# obc.net
KiCad netlist of a schematic drawn in EAGLE
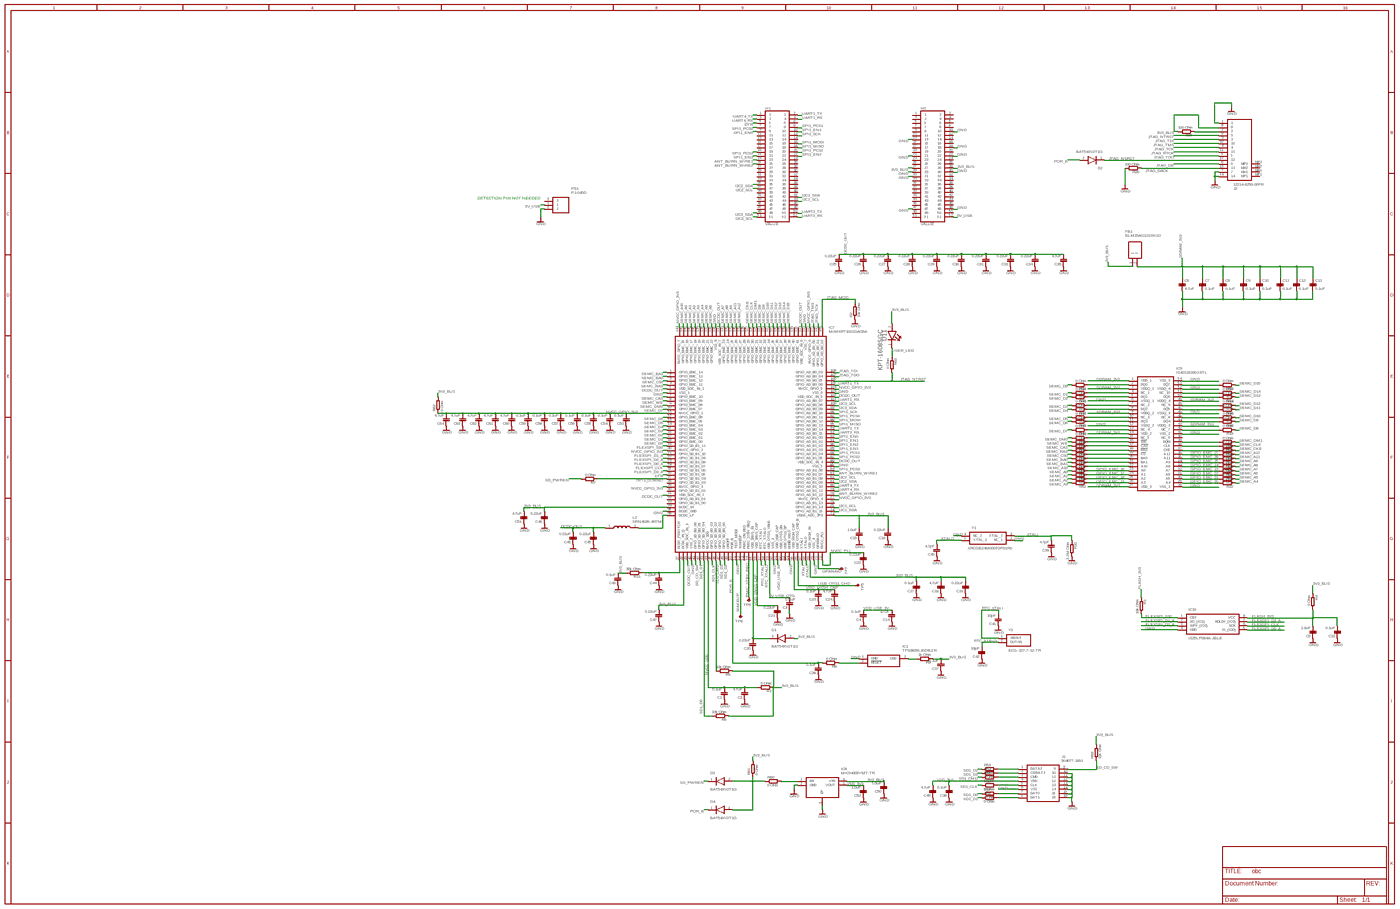
[diagram p0: schematic, sheet 1, overview]
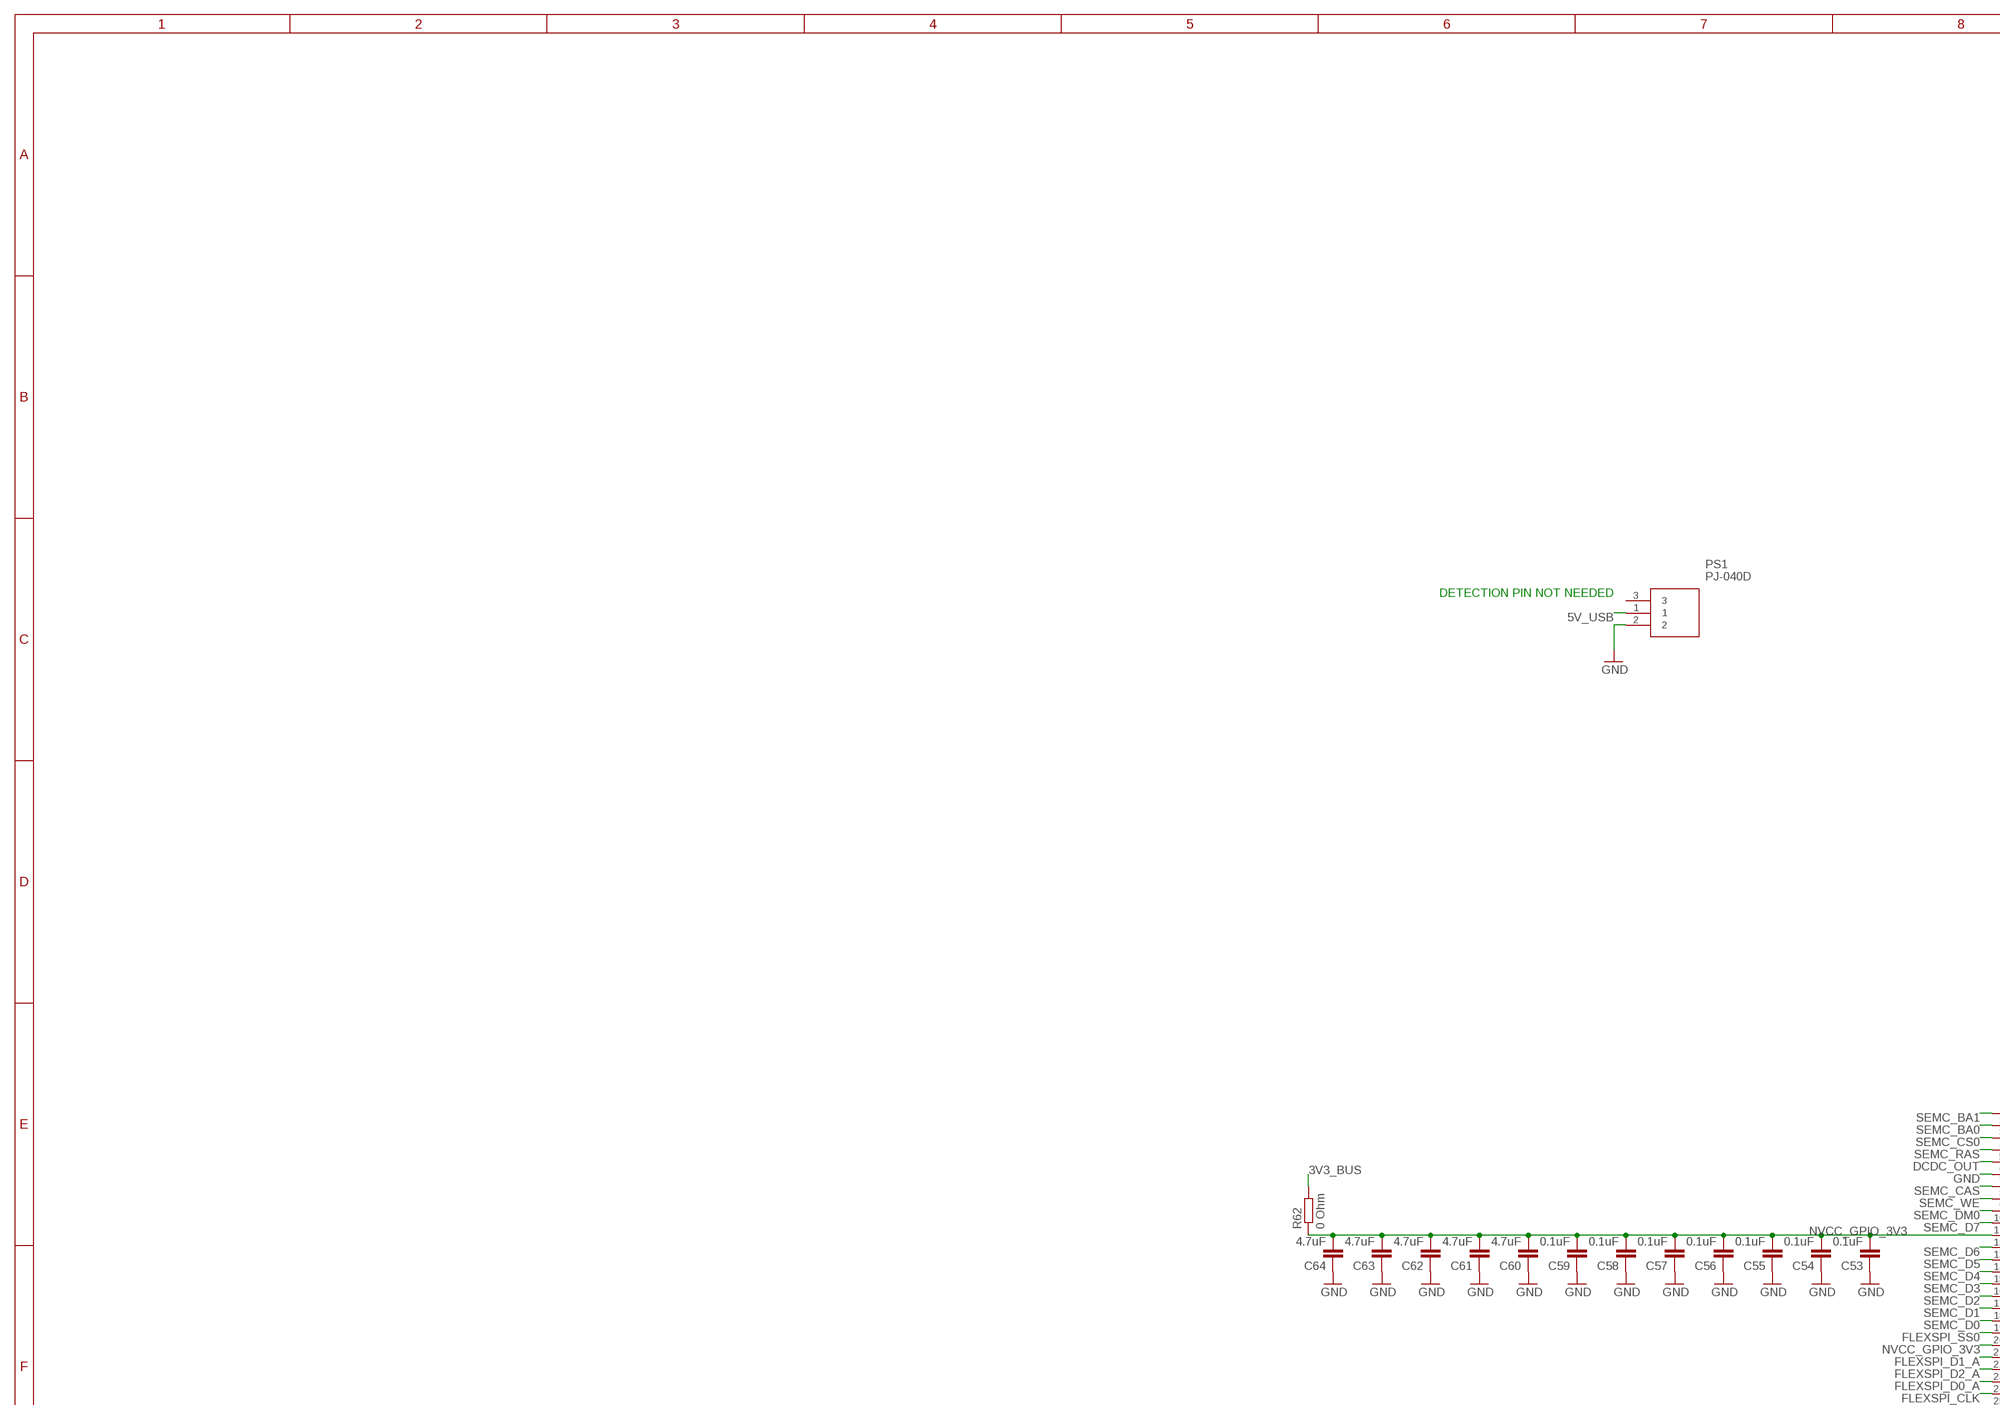
[diagram p1: schematic, sheet 1, part 1 of 4]
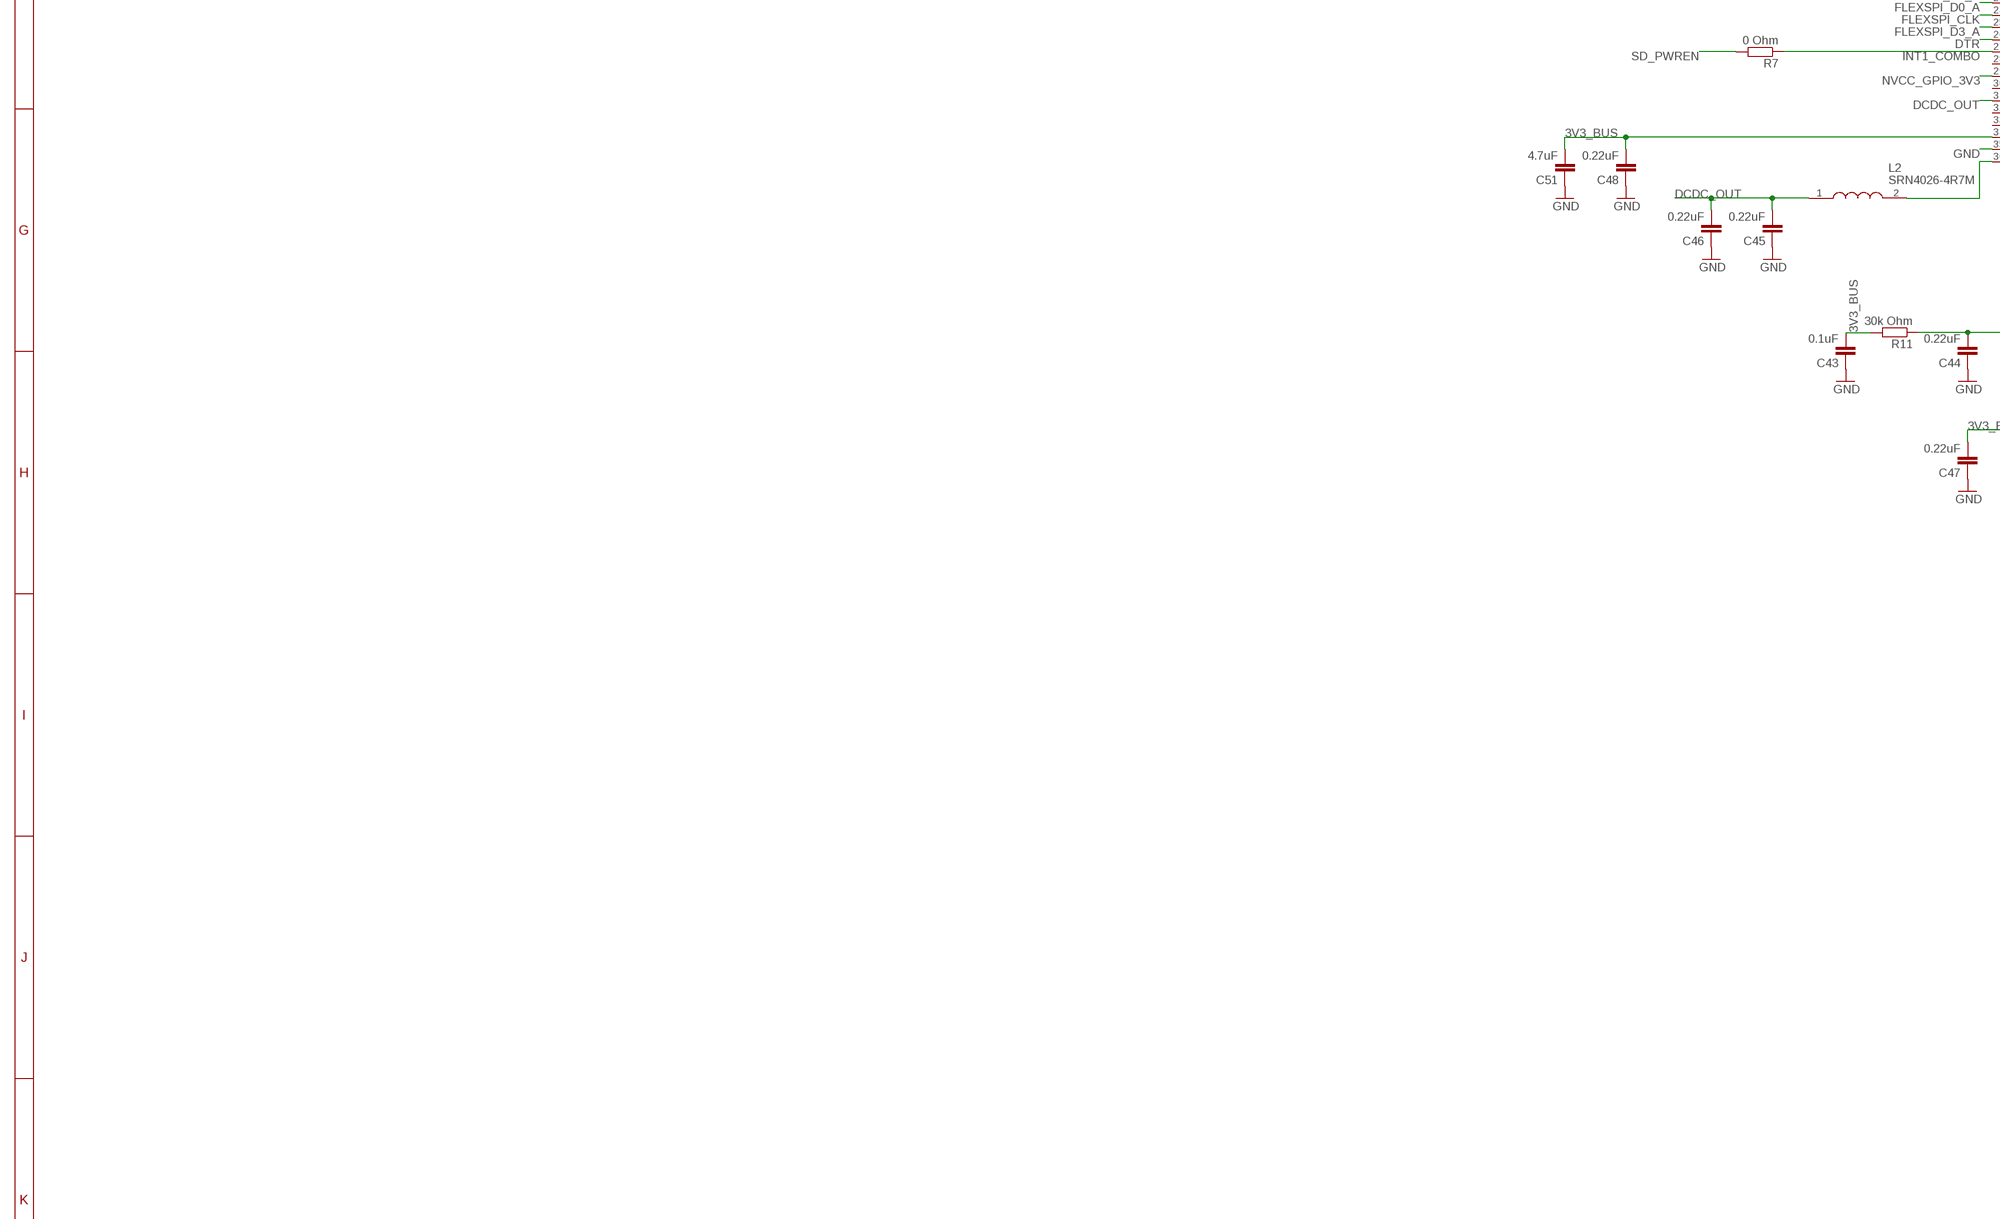
[diagram p2: schematic, sheet 1, part 2 of 4]
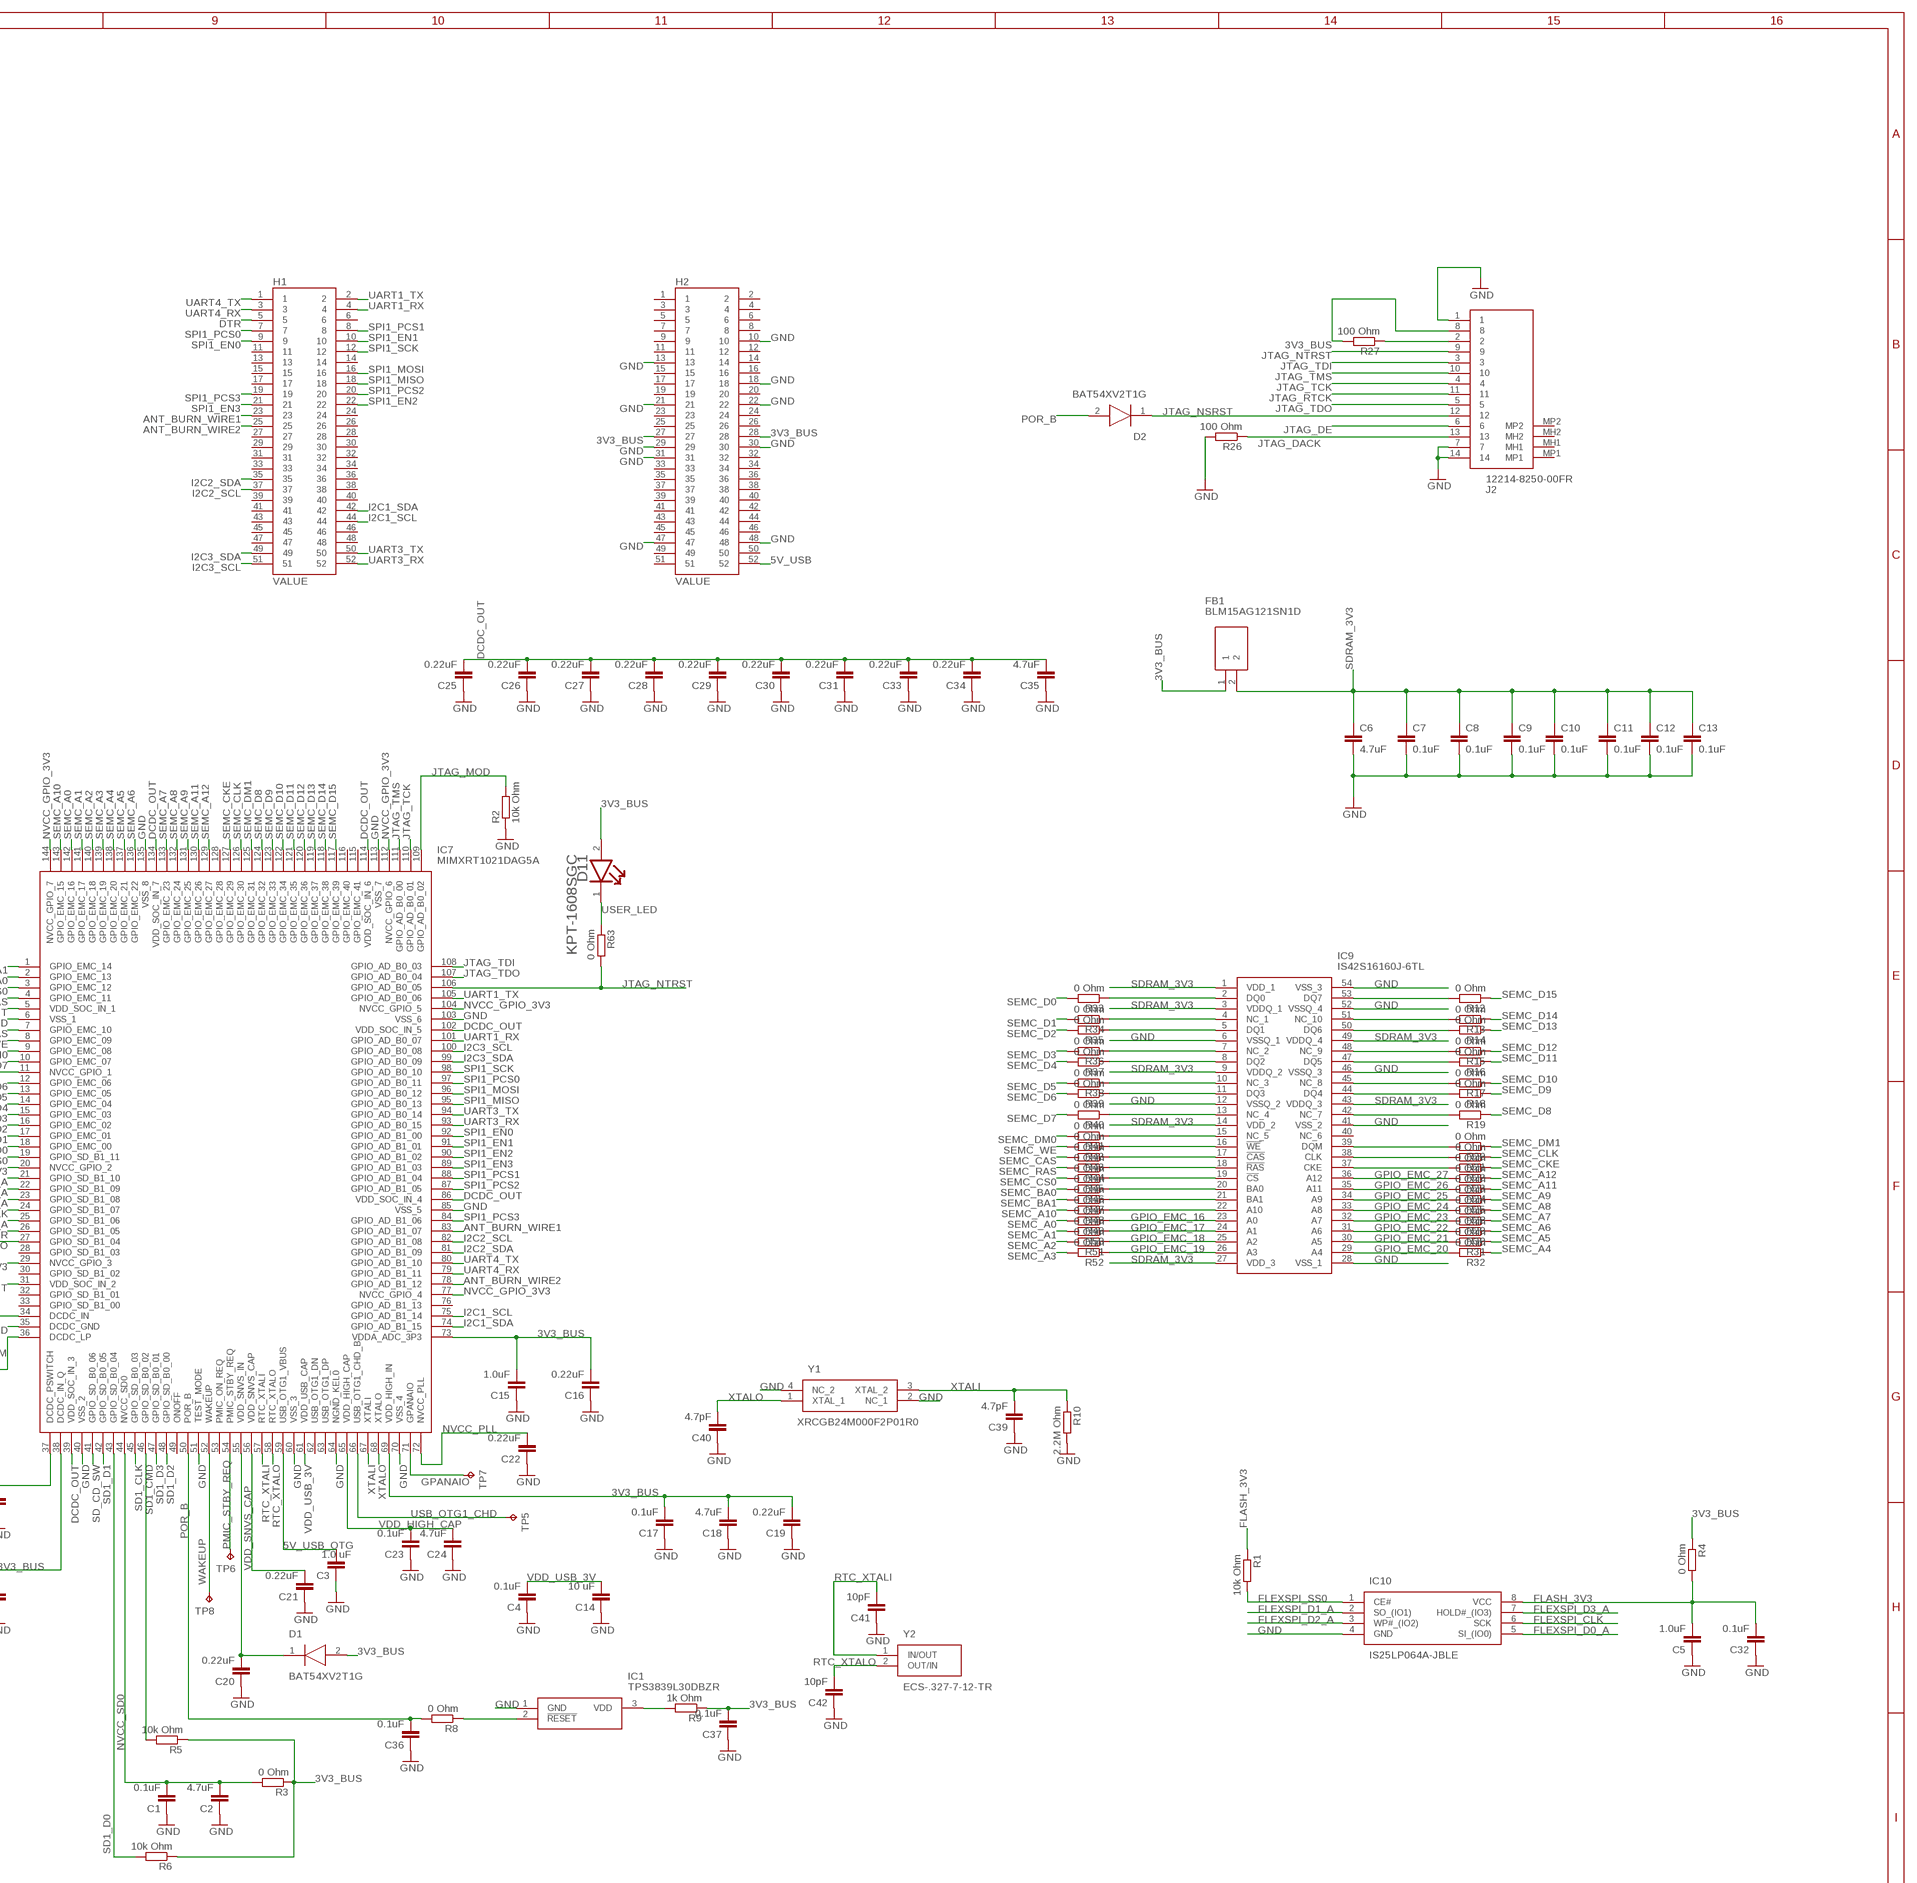
[diagram p3: schematic, sheet 1, part 3 of 4]
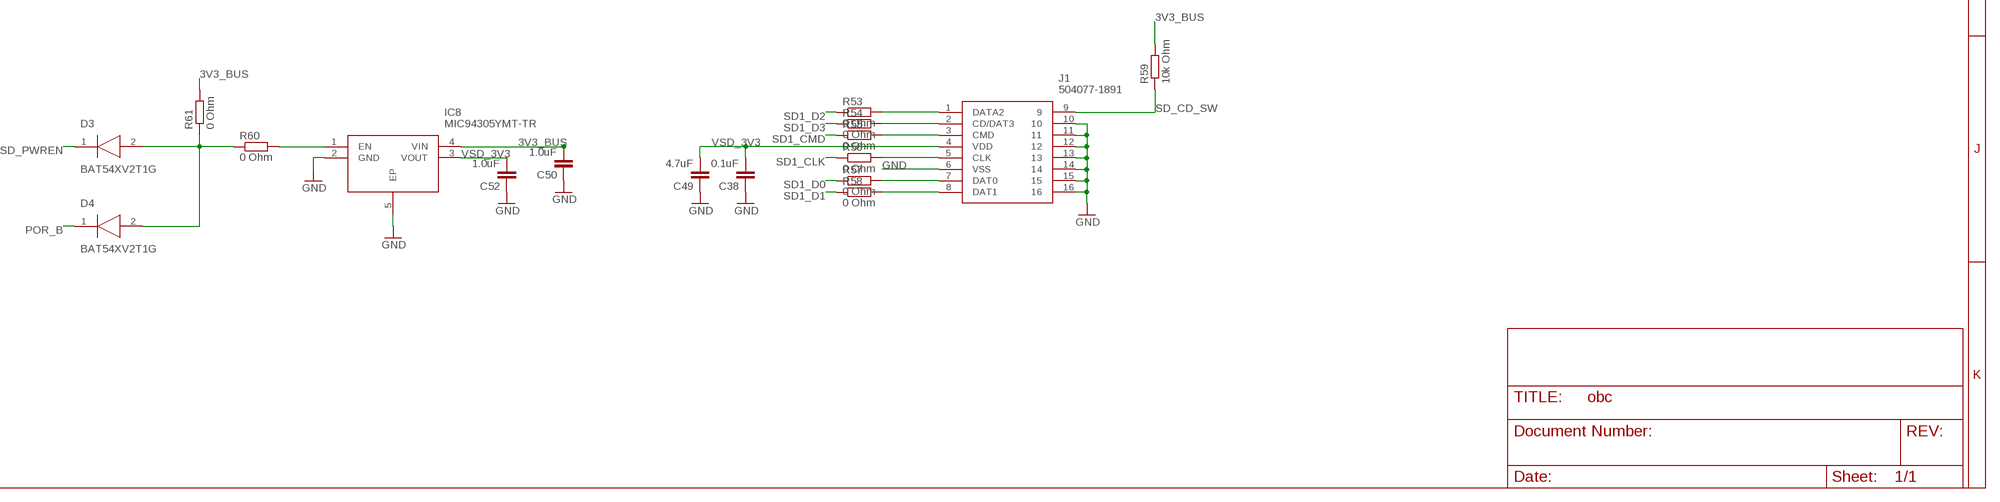
[diagram p4: schematic, sheet 1, part 4 of 4]

(export (version "E")
  (design (tool "Eeschema 10.0.6"))
  (components
    (comp (ref "C1")
      (value "0.1uF")
      (footprint "eagle-import:C0402K")
      (libsource (lib "eagle-import") (part "C-EUC0402K"))
    )
    (comp (ref "C2")
      (value "4.7uF")
      (footprint "eagle-import:C0402K")
      (libsource (lib "eagle-import") (part "C-EUC0402K"))
    )
    (comp (ref "C3")
      (value "1.0 uF")
      (footprint "eagle-import:C0402K")
      (libsource (lib "eagle-import") (part "C-EUC0402K"))
    )
    (comp (ref "C4")
      (value "0.1uF")
      (footprint "eagle-import:C0402K")
      (libsource (lib "eagle-import") (part "C-EUC0402K"))
    )
    (comp (ref "C5")
      (value "1.0uF")
      (footprint "eagle-import:C0402K")
      (libsource (lib "eagle-import") (part "C-EUC0402K"))
    )
    (comp (ref "C6")
      (value "4.7uF")
      (footprint "eagle-import:C0402K")
      (libsource (lib "eagle-import") (part "C-EUC0402K"))
    )
    (comp (ref "C7")
      (value "0.1uF")
      (footprint "eagle-import:C0402K")
      (libsource (lib "eagle-import") (part "C-EUC0402K"))
    )
    (comp (ref "C8")
      (value "0.1uF")
      (footprint "eagle-import:C0402K")
      (libsource (lib "eagle-import") (part "C-EUC0402K"))
    )
    (comp (ref "C9")
      (value "0.1uF")
      (footprint "eagle-import:C0402K")
      (libsource (lib "eagle-import") (part "C-EUC0402K"))
    )
    (comp (ref "C10")
      (value "0.1uF")
      (footprint "eagle-import:C0402K")
      (libsource (lib "eagle-import") (part "C-EUC0402K"))
    )
    (comp (ref "C11")
      (value "0.1uF")
      (footprint "eagle-import:C0402K")
      (libsource (lib "eagle-import") (part "C-EUC0402K"))
    )
    (comp (ref "C12")
      (value "0.1uF")
      (footprint "eagle-import:C0402K")
      (libsource (lib "eagle-import") (part "C-EUC0402K"))
    )
    (comp (ref "C13")
      (value "0.1uF")
      (footprint "eagle-import:C0402K")
      (libsource (lib "eagle-import") (part "C-EUC0402K"))
    )
    (comp (ref "C14")
      (value "10 uF")
      (footprint "eagle-import:C0402K")
      (libsource (lib "eagle-import") (part "C-EUC0402K"))
    )
    (comp (ref "C15")
      (value "1.0uF")
      (footprint "eagle-import:C0402K")
      (libsource (lib "eagle-import") (part "C-EUC0402K"))
    )
    (comp (ref "C16")
      (value "0.22uF")
      (footprint "eagle-import:C0402K")
      (libsource (lib "eagle-import") (part "C-EUC0402K"))
    )
    (comp (ref "C17")
      (value "0.1uF")
      (footprint "eagle-import:C0402K")
      (libsource (lib "eagle-import") (part "C-EUC0402K"))
    )
    (comp (ref "C18")
      (value "4.7uF")
      (footprint "eagle-import:C0402K")
      (libsource (lib "eagle-import") (part "C-EUC0402K"))
    )
    (comp (ref "C19")
      (value "0.22uF")
      (footprint "eagle-import:C0402K")
      (libsource (lib "eagle-import") (part "C-EUC0402K"))
    )
    (comp (ref "C20")
      (value "0.22uF")
      (footprint "eagle-import:C0402K")
      (libsource (lib "eagle-import") (part "C-EUC0402K"))
    )
    (comp (ref "C21")
      (value "0.22uF")
      (footprint "eagle-import:C0402K")
      (libsource (lib "eagle-import") (part "C-EUC0402K"))
    )
    (comp (ref "C22")
      (value "0.22uF")
      (footprint "eagle-import:C0402K")
      (libsource (lib "eagle-import") (part "C-EUC0402K"))
    )
    (comp (ref "C23")
      (value "0.1uF")
      (footprint "eagle-import:C0402K")
      (libsource (lib "eagle-import") (part "C-EUC0402K"))
    )
    (comp (ref "C24")
      (value "4.7uF")
      (footprint "eagle-import:C0402K")
      (libsource (lib "eagle-import") (part "C-EUC0402K"))
    )
    (comp (ref "C25")
      (value "0.22uF")
      (footprint "eagle-import:C0402K")
      (libsource (lib "eagle-import") (part "C-EUC0402K"))
    )
    (comp (ref "C26")
      (value "0.22uF")
      (footprint "eagle-import:C0402K")
      (libsource (lib "eagle-import") (part "C-EUC0402K"))
    )
    (comp (ref "C27")
      (value "0.22uF")
      (footprint "eagle-import:C0402K")
      (libsource (lib "eagle-import") (part "C-EUC0402K"))
    )
    (comp (ref "C28")
      (value "0.22uF")
      (footprint "eagle-import:C0402K")
      (libsource (lib "eagle-import") (part "C-EUC0402K"))
    )
    (comp (ref "C29")
      (value "0.22uF")
      (footprint "eagle-import:C0402K")
      (libsource (lib "eagle-import") (part "C-EUC0402K"))
    )
    (comp (ref "C30")
      (value "0.22uF")
      (footprint "eagle-import:C0402K")
      (libsource (lib "eagle-import") (part "C-EUC0402K"))
    )
    (comp (ref "C31")
      (value "0.22uF")
      (footprint "eagle-import:C0402K")
      (libsource (lib "eagle-import") (part "C-EUC0402K"))
    )
    (comp (ref "C32")
      (value "0.1uF")
      (footprint "eagle-import:C0402K")
      (libsource (lib "eagle-import") (part "C-EUC0402K"))
    )
    (comp (ref "C33")
      (value "0.22uF")
      (footprint "eagle-import:C0402K")
      (libsource (lib "eagle-import") (part "C-EUC0402K"))
    )
    (comp (ref "C34")
      (value "0.22uF")
      (footprint "eagle-import:C0402K")
      (libsource (lib "eagle-import") (part "C-EUC0402K"))
    )
    (comp (ref "C35")
      (value "4.7uF")
      (footprint "eagle-import:C0402K")
      (libsource (lib "eagle-import") (part "C-EUC0402K"))
    )
    (comp (ref "C36")
      (value "0.1uF")
      (footprint "eagle-import:C0402K")
      (libsource (lib "eagle-import") (part "C-EUC0402K"))
    )
    (comp (ref "C37")
      (value "0.1uF")
      (footprint "eagle-import:C0402K")
      (libsource (lib "eagle-import") (part "C-EUC0402K"))
    )
    (comp (ref "C38")
      (value "0.1uF")
      (footprint "eagle-import:C0402K")
      (libsource (lib "eagle-import") (part "C-EUC0402K"))
    )
    (comp (ref "C39")
      (value "4.7pF")
      (footprint "eagle-import:C0402K")
      (libsource (lib "eagle-import") (part "C-EUC0402K"))
    )
    (comp (ref "C40")
      (value "4.7pF")
      (footprint "eagle-import:C0402K")
      (libsource (lib "eagle-import") (part "C-EUC0402K"))
    )
    (comp (ref "C41")
      (value "10pF")
      (footprint "eagle-import:C0402K")
      (libsource (lib "eagle-import") (part "C-EUC0402K"))
    )
    (comp (ref "C42")
      (value "10pF")
      (footprint "eagle-import:C0402K")
      (libsource (lib "eagle-import") (part "C-EUC0402K"))
    )
    (comp (ref "C43")
      (value "0.1uF")
      (footprint "eagle-import:C0402K")
      (libsource (lib "eagle-import") (part "C-EUC0402K"))
    )
    (comp (ref "C44")
      (value "0.22uF")
      (footprint "eagle-import:C0402K")
      (libsource (lib "eagle-import") (part "C-EUC0402K"))
    )
    (comp (ref "C45")
      (value "0.22uF")
      (footprint "eagle-import:C0402K")
      (libsource (lib "eagle-import") (part "C-EUC0402K"))
    )
    (comp (ref "C46")
      (value "0.22uF")
      (footprint "eagle-import:C0402K")
      (libsource (lib "eagle-import") (part "C-EUC0402K"))
    )
    (comp (ref "C47")
      (value "0.22uF")
      (footprint "eagle-import:C0402K")
      (libsource (lib "eagle-import") (part "C-EUC0402K"))
    )
    (comp (ref "C48")
      (value "0.22uF")
      (footprint "eagle-import:C0402K")
      (libsource (lib "eagle-import") (part "C-EUC0402K"))
    )
    (comp (ref "C49")
      (value "4.7uF")
      (footprint "eagle-import:C0402K")
      (libsource (lib "eagle-import") (part "C-EUC0402K"))
    )
    (comp (ref "C50")
      (value "1.0uF")
      (footprint "eagle-import:C0402K")
      (libsource (lib "eagle-import") (part "C-EUC0402K"))
    )
    (comp (ref "C51")
      (value "4.7uF")
      (footprint "eagle-import:C0402K")
      (libsource (lib "eagle-import") (part "C-EUC0402K"))
    )
    (comp (ref "C52")
      (value "1.0uF")
      (footprint "eagle-import:C0402K")
      (libsource (lib "eagle-import") (part "C-EUC0402K"))
    )
    (comp (ref "C53")
      (value "0.1uF")
      (footprint "eagle-import:C0402K")
      (libsource (lib "eagle-import") (part "C-EUC0402K"))
    )
    (comp (ref "C54")
      (value "0.1uF")
      (footprint "eagle-import:C0402K")
      (libsource (lib "eagle-import") (part "C-EUC0402K"))
    )
    (comp (ref "C55")
      (value "0.1uF")
      (footprint "eagle-import:C0402K")
      (libsource (lib "eagle-import") (part "C-EUC0402K"))
    )
    (comp (ref "C56")
      (value "0.1uF")
      (footprint "eagle-import:C0402K")
      (libsource (lib "eagle-import") (part "C-EUC0402K"))
    )
    (comp (ref "C57")
      (value "0.1uF")
      (footprint "eagle-import:C0402K")
      (libsource (lib "eagle-import") (part "C-EUC0402K"))
    )
    (comp (ref "C58")
      (value "0.1uF")
      (footprint "eagle-import:C0402K")
      (libsource (lib "eagle-import") (part "C-EUC0402K"))
    )
    (comp (ref "C59")
      (value "0.1uF")
      (footprint "eagle-import:C0402K")
      (libsource (lib "eagle-import") (part "C-EUC0402K"))
    )
    (comp (ref "C60")
      (value "4.7uF")
      (footprint "eagle-import:C0402K")
      (libsource (lib "eagle-import") (part "C-EUC0402K"))
    )
    (comp (ref "C61")
      (value "4.7uF")
      (footprint "eagle-import:C0402K")
      (libsource (lib "eagle-import") (part "C-EUC0402K"))
    )
    (comp (ref "C62")
      (value "4.7uF")
      (footprint "eagle-import:C0402K")
      (libsource (lib "eagle-import") (part "C-EUC0402K"))
    )
    (comp (ref "C63")
      (value "4.7uF")
      (footprint "eagle-import:C0402K")
      (libsource (lib "eagle-import") (part "C-EUC0402K"))
    )
    (comp (ref "C64")
      (value "4.7uF")
      (footprint "eagle-import:C0402K")
      (libsource (lib "eagle-import") (part "C-EUC0402K"))
    )
    (comp (ref "D1")
      (value "BAT54XV2T1G")
      (footprint "eagle-import:SODFL1608X70N")
      (fields (field (name "MOUSER_PART_NUMBER") "863-BAT54XV2T1G"))
      (libsource (lib "eagle-import") (part "BAT54XV2T1G"))
    )
    (comp (ref "D2")
      (value "BAT54XV2T1G")
      (footprint "eagle-import:SODFL1608X70N")
      (fields (field (name "MOUSER_PART_NUMBER") "863-BAT54XV2T1G"))
      (libsource (lib "eagle-import") (part "BAT54XV2T1G"))
    )
    (comp (ref "D3")
      (value "BAT54XV2T1G")
      (footprint "eagle-import:SODFL1608X70N")
      (fields (field (name "MOUSER_PART_NUMBER") "863-BAT54XV2T1G"))
      (libsource (lib "eagle-import") (part "BAT54XV2T1G"))
    )
    (comp (ref "D4")
      (value "BAT54XV2T1G")
      (footprint "eagle-import:SODFL1608X70N")
      (fields (field (name "MOUSER_PART_NUMBER") "863-BAT54XV2T1G"))
      (libsource (lib "eagle-import") (part "BAT54XV2T1G"))
    )
    (comp (ref "D11")
      (value "KINGBRIGHT_KPT-1608SGCKINGBRIGHT_KPT-1608SGC_0_0")
      (footprint "eagle-import:KINGBRIGHT_KPT-1608SGC_0")
      (fields (field (name "MF") "Kingbright") (field (name "MPN") "KPT-1608SGC"))
      (libsource (lib "eagle-import") (part "KINGBRIGHT_KPT-1608SGCKINGBRIGHT_KPT-1608SGC_0_0"))
    )
    (comp (ref "FB1")
      (value "BLM15AG121SN1D")
      (footprint "eagle-import:NFZ15SG152SN10B")
      (fields (field (name "MOUSER_PART_NUMBER") "81-BLM15AG121SN1D"))
      (libsource (lib "eagle-import") (part "BLM15AG121SN1D"))
    )
    (comp (ref "H1")
      (value "ESQ-126-39-G-D")
      (footprint "eagle-import:SAMTEC_ESQ-126-39-G-D")
      (fields (field (name "DIGI-KEY_PART_NUMBER") "SAM10462-ND") (field (name "MF") "Samtec"))
      (libsource (lib "eagle-import") (part "ESQ-126-39-G-D"))
    )
    (comp (ref "H2")
      (value "ESQ-126-39-G-D")
      (footprint "eagle-import:SAMTEC_ESQ-126-39-G-D")
      (fields (field (name "DIGI-KEY_PART_NUMBER") "SAM10462-ND") (field (name "MF") "Samtec"))
      (libsource (lib "eagle-import") (part "ESQ-126-39-G-D"))
    )
    (comp (ref "IC1")
      (value "TPS3839L30DBZR")
      (footprint "eagle-import:SOT95P237X112-3N")
      (fields (field (name "MOUSER_PART_NUMBER") "595-TPS3839L30DBZR"))
      (libsource (lib "eagle-import") (part "TPS3839L30DBZR"))
    )
    (comp (ref "IC7")
      (value "MIMXRT1021DAG5A")
      (footprint "eagle-import:QFP50P2200X2200X160-144N")
      (fields (field (name "MOUSER_PART_NUMBER") "771-MIMXRT1021DAG5A"))
      (libsource (lib "eagle-import") (part "MIMXRT1021DAG5A"))
    )
    (comp (ref "IC8")
      (value "MIC94305YMT-TR")
      (footprint "eagle-import:SON50P160X120X60-5N")
      (fields (field (name "MOUSER_PART_NUMBER") "998-MIC94305YMTTR"))
      (libsource (lib "eagle-import") (part "MIC94305YMT-TR"))
    )
    (comp (ref "IC9")
      (value "IS42S16160J-6TL")
      (footprint "eagle-import:SOP80P1176X120-54N")
      (fields (field (name "MOUSER_PART_NUMBER") "870-IS42S16160J-6TL"))
      (libsource (lib "eagle-import") (part "IS42S16160J-6TL"))
    )
    (comp (ref "IC10")
      (value "IS25LP064A-JBLE")
      (footprint "eagle-import:SOIC127P790X216-8N")
      (libsource (lib "eagle-import") (part "IS25LP064A-JBLE"))
    )
    (comp (ref "J1")
      (value "504077-1891")
      (footprint "eagle-import:5040771891")
      (fields (field (name "MOUSER_PART_NUMBER") "538-504077-1891"))
      (libsource (lib "eagle-import") (part "504077-1891"))
    )
    (comp (ref "J2")
      (value "12214-8250-00FR")
      (footprint "eagle-import:12214825000FR")
      (fields (field (name "MOUSER_PART_NUMBER") "517-12214-825000FR"))
      (libsource (lib "eagle-import") (part "12214-8250-00FR"))
    )
    (comp (ref "L2")
      (value "SRN4026-4R7M")
      (footprint "eagle-import:SRN4026")
      (fields (field (name "MOUSER_PART_NUMBER") "652-SRN4026-4R7M"))
      (libsource (lib "eagle-import") (part "SRN4026-4R7M"))
    )
    (comp (ref "PS1")
      (value "PJ-040D")
      (footprint "eagle-import:PJ040D")
      (fields (field (name "MOUSER_PART_NUMBER") "490-PJ-040D"))
      (libsource (lib "eagle-import") (part "PJ-040D"))
    )
    (comp (ref "R1")
      (value "10k Ohm")
      (footprint "eagle-import:R0402")
      (libsource (lib "eagle-import") (part "R-EU_R0402"))
    )
    (comp (ref "R2")
      (value "10k Ohm")
      (footprint "eagle-import:R0402")
      (libsource (lib "eagle-import") (part "R-EU_R0402"))
    )
    (comp (ref "R3")
      (value "0 Ohm")
      (footprint "eagle-import:R0402")
      (libsource (lib "eagle-import") (part "R-EU_R0402"))
    )
    (comp (ref "R4")
      (value "0 Ohm")
      (footprint "eagle-import:R0402")
      (libsource (lib "eagle-import") (part "R-EU_R0402"))
    )
    (comp (ref "R5")
      (value "10k Ohm")
      (footprint "eagle-import:R0402")
      (libsource (lib "eagle-import") (part "R-EU_R0402"))
    )
    (comp (ref "R6")
      (value "10k Ohm")
      (footprint "eagle-import:R0402")
      (libsource (lib "eagle-import") (part "R-EU_R0402"))
    )
    (comp (ref "R7")
      (value "0 Ohm")
      (footprint "eagle-import:R0402")
      (libsource (lib "eagle-import") (part "R-EU_R0402"))
    )
    (comp (ref "R8")
      (value "0 Ohm")
      (footprint "eagle-import:R0402")
      (libsource (lib "eagle-import") (part "R-EU_R0402"))
    )
    (comp (ref "R9")
      (value "1k Ohm")
      (footprint "eagle-import:R0402")
      (libsource (lib "eagle-import") (part "R-EU_R0402"))
    )
    (comp (ref "R10")
      (value "2.2M Ohm")
      (footprint "eagle-import:R0402")
      (libsource (lib "eagle-import") (part "R-EU_R0402"))
    )
    (comp (ref "R11")
      (value "30k Ohm")
      (footprint "eagle-import:R0402")
      (libsource (lib "eagle-import") (part "R-EU_R0402"))
    )
    (comp (ref "R12")
      (value "0 Ohm")
      (footprint "eagle-import:R0402")
      (libsource (lib "eagle-import") (part "R-EU_R0402"))
    )
    (comp (ref "R13")
      (value "0 Ohm")
      (footprint "eagle-import:R0402")
      (libsource (lib "eagle-import") (part "R-EU_R0402"))
    )
    (comp (ref "R14")
      (value "0 Ohm")
      (footprint "eagle-import:R0402")
      (libsource (lib "eagle-import") (part "R-EU_R0402"))
    )
    (comp (ref "R15")
      (value "0 Ohm")
      (footprint "eagle-import:R0402")
      (libsource (lib "eagle-import") (part "R-EU_R0402"))
    )
    (comp (ref "R16")
      (value "0 Ohm")
      (footprint "eagle-import:R0402")
      (libsource (lib "eagle-import") (part "R-EU_R0402"))
    )
    (comp (ref "R17")
      (value "0 Ohm")
      (footprint "eagle-import:R0402")
      (libsource (lib "eagle-import") (part "R-EU_R0402"))
    )
    (comp (ref "R18")
      (value "0 Ohm")
      (footprint "eagle-import:R0402")
      (libsource (lib "eagle-import") (part "R-EU_R0402"))
    )
    (comp (ref "R19")
      (value "0 Ohm")
      (footprint "eagle-import:R0402")
      (libsource (lib "eagle-import") (part "R-EU_R0402"))
    )
    (comp (ref "R20")
      (value "0 Ohm")
      (footprint "eagle-import:R0402")
      (libsource (lib "eagle-import") (part "R-EU_R0402"))
    )
    (comp (ref "R21")
      (value "0 Ohm")
      (footprint "eagle-import:R0402")
      (libsource (lib "eagle-import") (part "R-EU_R0402"))
    )
    (comp (ref "R22")
      (value "0 Ohm")
      (footprint "eagle-import:R0402")
      (libsource (lib "eagle-import") (part "R-EU_R0402"))
    )
    (comp (ref "R23")
      (value "0 Ohm")
      (footprint "eagle-import:R0402")
      (libsource (lib "eagle-import") (part "R-EU_R0402"))
    )
    (comp (ref "R24")
      (value "0 Ohm")
      (footprint "eagle-import:R0402")
      (libsource (lib "eagle-import") (part "R-EU_R0402"))
    )
    (comp (ref "R25")
      (value "0 Ohm")
      (footprint "eagle-import:R0402")
      (libsource (lib "eagle-import") (part "R-EU_R0402"))
    )
    (comp (ref "R26")
      (value "100 Ohm")
      (footprint "eagle-import:R0402")
      (libsource (lib "eagle-import") (part "R-EU_R0402"))
    )
    (comp (ref "R27")
      (value "100 Ohm")
      (footprint "eagle-import:R0402")
      (libsource (lib "eagle-import") (part "R-EU_R0402"))
    )
    (comp (ref "R28")
      (value "0 Ohm")
      (footprint "eagle-import:R0402")
      (libsource (lib "eagle-import") (part "R-EU_R0402"))
    )
    (comp (ref "R29")
      (value "0 Ohm")
      (footprint "eagle-import:R0402")
      (libsource (lib "eagle-import") (part "R-EU_R0402"))
    )
    (comp (ref "R30")
      (value "0 Ohm")
      (footprint "eagle-import:R0402")
      (libsource (lib "eagle-import") (part "R-EU_R0402"))
    )
    (comp (ref "R31")
      (value "0 Ohm")
      (footprint "eagle-import:R0402")
      (libsource (lib "eagle-import") (part "R-EU_R0402"))
    )
    (comp (ref "R32")
      (value "0 Ohm")
      (footprint "eagle-import:R0402")
      (libsource (lib "eagle-import") (part "R-EU_R0402"))
    )
    (comp (ref "R33")
      (value "0 Ohm")
      (footprint "eagle-import:R0402")
      (libsource (lib "eagle-import") (part "R-EU_R0402"))
    )
    (comp (ref "R34")
      (value "0 Ohm")
      (footprint "eagle-import:R0402")
      (libsource (lib "eagle-import") (part "R-EU_R0402"))
    )
    (comp (ref "R35")
      (value "0 Ohm")
      (footprint "eagle-import:R0402")
      (libsource (lib "eagle-import") (part "R-EU_R0402"))
    )
    (comp (ref "R36")
      (value "0 Ohm")
      (footprint "eagle-import:R0402")
      (libsource (lib "eagle-import") (part "R-EU_R0402"))
    )
    (comp (ref "R37")
      (value "0 Ohm")
      (footprint "eagle-import:R0402")
      (libsource (lib "eagle-import") (part "R-EU_R0402"))
    )
    (comp (ref "R38")
      (value "0 Ohm")
      (footprint "eagle-import:R0402")
      (libsource (lib "eagle-import") (part "R-EU_R0402"))
    )
    (comp (ref "R39")
      (value "0 Ohm")
      (footprint "eagle-import:R0402")
      (libsource (lib "eagle-import") (part "R-EU_R0402"))
    )
    (comp (ref "R40")
      (value "0 Ohm")
      (footprint "eagle-import:R0402")
      (libsource (lib "eagle-import") (part "R-EU_R0402"))
    )
    (comp (ref "R41")
      (value "0 Ohm")
      (footprint "eagle-import:R0402")
      (libsource (lib "eagle-import") (part "R-EU_R0402"))
    )
    (comp (ref "R42")
      (value "0 Ohm")
      (footprint "eagle-import:R0402")
      (libsource (lib "eagle-import") (part "R-EU_R0402"))
    )
    (comp (ref "R43")
      (value "0 Ohm")
      (footprint "eagle-import:R0402")
      (libsource (lib "eagle-import") (part "R-EU_R0402"))
    )
    (comp (ref "R44")
      (value "0 Ohm")
      (footprint "eagle-import:R0402")
      (libsource (lib "eagle-import") (part "R-EU_R0402"))
    )
    (comp (ref "R45")
      (value "0 Ohm")
      (footprint "eagle-import:R0402")
      (libsource (lib "eagle-import") (part "R-EU_R0402"))
    )
    (comp (ref "R46")
      (value "0 Ohm")
      (footprint "eagle-import:R0402")
      (libsource (lib "eagle-import") (part "R-EU_R0402"))
    )
    (comp (ref "R47")
      (value "0 Ohm")
      (footprint "eagle-import:R0402")
      (libsource (lib "eagle-import") (part "R-EU_R0402"))
    )
    (comp (ref "R48")
      (value "0 Ohm")
      (footprint "eagle-import:R0402")
      (libsource (lib "eagle-import") (part "R-EU_R0402"))
    )
    (comp (ref "R49")
      (value "0 Ohm")
      (footprint "eagle-import:R0402")
      (libsource (lib "eagle-import") (part "R-EU_R0402"))
    )
    (comp (ref "R50")
      (value "0 Ohm")
      (footprint "eagle-import:R0402")
      (libsource (lib "eagle-import") (part "R-EU_R0402"))
    )
    (comp (ref "R51")
      (value "0 Ohm")
      (footprint "eagle-import:R0402")
      (libsource (lib "eagle-import") (part "R-EU_R0402"))
    )
    (comp (ref "R52")
      (value "0 Ohm")
      (footprint "eagle-import:R0402")
      (libsource (lib "eagle-import") (part "R-EU_R0402"))
    )
    (comp (ref "R53")
      (value "0 Ohm")
      (footprint "eagle-import:R0402")
      (libsource (lib "eagle-import") (part "R-EU_R0402"))
    )
    (comp (ref "R54")
      (value "0 Ohm")
      (footprint "eagle-import:R0402")
      (libsource (lib "eagle-import") (part "R-EU_R0402"))
    )
    (comp (ref "R55")
      (value "0 Ohm")
      (footprint "eagle-import:R0402")
      (libsource (lib "eagle-import") (part "R-EU_R0402"))
    )
    (comp (ref "R56")
      (value "0 Ohm")
      (footprint "eagle-import:R0402")
      (libsource (lib "eagle-import") (part "R-EU_R0402"))
    )
    (comp (ref "R57")
      (value "0 Ohm")
      (footprint "eagle-import:R0402")
      (libsource (lib "eagle-import") (part "R-EU_R0402"))
    )
    (comp (ref "R58")
      (value "0 Ohm")
      (footprint "eagle-import:R0402")
      (libsource (lib "eagle-import") (part "R-EU_R0402"))
    )
    (comp (ref "R59")
      (value "10k Ohm")
      (footprint "eagle-import:R0402")
      (libsource (lib "eagle-import") (part "R-EU_R0402"))
    )
    (comp (ref "R60")
      (value "0 Ohm")
      (footprint "eagle-import:R0402")
      (libsource (lib "eagle-import") (part "R-EU_R0402"))
    )
    (comp (ref "R61")
      (value "0 Ohm")
      (footprint "eagle-import:R0402")
      (libsource (lib "eagle-import") (part "R-EU_R0402"))
    )
    (comp (ref "R62")
      (value "0 Ohm")
      (footprint "eagle-import:R0402")
      (libsource (lib "eagle-import") (part "R-EU_R0402"))
    )
    (comp (ref "R63")
      (value "0 Ohm")
      (footprint "eagle-import:R0402")
      (libsource (lib "eagle-import") (part "R-EU_R0402"))
    )
    (comp (ref "TP5")
      (value "TPTP06R")
      (footprint "eagle-import:TP06R")
      (libsource (lib "eagle-import") (part "TPTP06R"))
    )
    (comp (ref "TP6")
      (value "TPTP06R")
      (footprint "eagle-import:TP06R")
      (libsource (lib "eagle-import") (part "TPTP06R"))
    )
    (comp (ref "TP7")
      (value "TPTP06R")
      (footprint "eagle-import:TP06R")
      (libsource (lib "eagle-import") (part "TPTP06R"))
    )
    (comp (ref "TP8")
      (value "TPTP06R")
      (footprint "eagle-import:TP06R")
      (libsource (lib "eagle-import") (part "TPTP06R"))
    )
    (comp (ref "Y1")
      (value "XRCGB24M000F2P01R0")
      (footprint "eagle-import:XRCGB24M000F2P01R0")
      (fields (field (name "MOUSER_PART_NUMBER") "81-XRCGB24M000F2P01R"))
      (libsource (lib "eagle-import") (part "XRCGB24M000F2P01R0"))
    )
    (comp (ref "Y2")
      (value "ECS-.327-7-12-TR")
      (footprint "eagle-import:ECS327712TR")
      (fields (field (name "MOUSER_PART_NUMBER") "520-ECS-.327-7-12-TR"))
      (libsource (lib "eagle-import") (part "ECS-.327-7-12-TR"))
    )
  )
  (nets
    (net (code "1") (name "/3V3_BUS") (class "Default")
      (node (ref "C15") (pin "2") (pinfunction "2_2") (pintype "passive"))
      (node (ref "C16") (pin "2") (pinfunction "2_2") (pintype "passive"))
      (node (ref "C17") (pin "2") (pinfunction "2_2") (pintype "passive"))
      (node (ref "C18") (pin "2") (pinfunction "2_2") (pintype "passive"))
      (node (ref "C19") (pin "2") (pinfunction "2_2") (pintype "passive"))
      (node (ref "C37") (pin "2") (pinfunction "2_2") (pintype "passive"))
      (node (ref "C43") (pin "2") (pinfunction "2_2") (pintype "passive"))
      (node (ref "C47") (pin "2") (pinfunction "2_2") (pintype "passive"))
      (node (ref "C48") (pin "2") (pinfunction "2_2") (pintype "passive"))
      (node (ref "C50") (pin "2") (pinfunction "2_2") (pintype "passive"))
      (node (ref "C51") (pin "2") (pinfunction "2_2") (pintype "passive"))
      (node (ref "D1") (pin "2") (pinfunction "A_2") (pintype "bidirectional"))
      (node (ref "D11") (pin "2") (pinfunction "ANODE_2") (pintype "passive"))
      (node (ref "FB1") (pin "1") (pinfunction "1_1") (pintype "bidirectional"))
      (node (ref "H2") (pin "27") (pinfunction "27_27") (pintype "passive"))
      (node (ref "H2") (pin "28") (pinfunction "28_28") (pintype "passive"))
      (node (ref "IC7") (pin "34") (pinfunction "DCDC_IN_34") (pintype "bidirectional"))
      (node (ref "IC7") (pin "38") (pinfunction "DCDC_IN_Q_38") (pintype "bidirectional"))
      (node (ref "IC7") (pin "69") (pinfunction "VDD_HIGH_IN_69") (pintype "bidirectional"))
      (node (ref "IC7") (pin "73") (pinfunction "VDDA_ADC_3P3_73") (pintype "bidirectional"))
      (node (ref "IC8") (pin "4") (pinfunction "VIN_4") (pintype "bidirectional"))
      (node (ref "J2") (pin "8") (pinfunction "8_8") (pintype "bidirectional"))
      (node (ref "R11") (pin "2") (pinfunction "2_2") (pintype "passive"))
      (node (ref "R27") (pin "2") (pinfunction "2_2") (pintype "passive"))
      (node (ref "R3") (pin "1") (pinfunction "1_1") (pintype "passive"))
      (node (ref "R4") (pin "1") (pinfunction "1_1") (pintype "passive"))
      (node (ref "R5") (pin "1") (pinfunction "1_1") (pintype "passive"))
      (node (ref "R59") (pin "2") (pinfunction "2_2") (pintype "passive"))
      (node (ref "R6") (pin "1") (pinfunction "1_1") (pintype "passive"))
      (node (ref "R61") (pin "2") (pinfunction "2_2") (pintype "passive"))
      (node (ref "R62") (pin "2") (pinfunction "2_2") (pintype "passive"))
      (node (ref "R9") (pin "1") (pinfunction "1_1") (pintype "passive"))
    )
    (net (code "2") (name "/5V_USB") (class "Default")
      (node (ref "H2") (pin "52") (pinfunction "52_52") (pintype "passive"))
      (node (ref "PS1") (pin "1") (pinfunction "1_1") (pintype "bidirectional"))
    )
    (net (code "3") (name "/5V_USB_OTG") (class "Default")
      (node (ref "C3") (pin "2") (pinfunction "2_2") (pintype "passive"))
      (node (ref "IC7") (pin "59") (pinfunction "USB_OTG1_VBUS_59") (pintype "bidirectional"))
    )
    (net (code "4") (name "/ANT_BURN_WIRE1") (class "Default")
      (node (ref "H1") (pin "23") (pinfunction "23_23") (pintype "passive"))
      (node (ref "IC7") (pin "83") (pinfunction "GPIO_AD_B1_07_83") (pintype "bidirectional"))
    )
    (net (code "5") (name "/ANT_BURN_WIRE2") (class "Default")
      (node (ref "H1") (pin "25") (pinfunction "25_25") (pintype "passive"))
      (node (ref "IC7") (pin "78") (pinfunction "GPIO_AD_B1_12_78") (pintype "bidirectional"))
    )
    (net (code "6") (name "/DCDC_OUT") (class "Default")
      (node (ref "C25") (pin "2") (pinfunction "2_2") (pintype "passive"))
      (node (ref "C26") (pin "2") (pinfunction "2_2") (pintype "passive"))
      (node (ref "C27") (pin "2") (pinfunction "2_2") (pintype "passive"))
      (node (ref "C28") (pin "2") (pinfunction "2_2") (pintype "passive"))
      (node (ref "C29") (pin "2") (pinfunction "2_2") (pintype "passive"))
      (node (ref "C30") (pin "2") (pinfunction "2_2") (pintype "passive"))
      (node (ref "C31") (pin "2") (pinfunction "2_2") (pintype "passive"))
      (node (ref "C33") (pin "2") (pinfunction "2_2") (pintype "passive"))
      (node (ref "C34") (pin "2") (pinfunction "2_2") (pintype "passive"))
      (node (ref "C35") (pin "2") (pinfunction "2_2") (pintype "passive"))
      (node (ref "C45") (pin "2") (pinfunction "2_2") (pintype "passive"))
      (node (ref "C46") (pin "2") (pinfunction "2_2") (pintype "passive"))
      (node (ref "IC7") (pin "102") (pinfunction "VDD_SOC_IN_5_102") (pintype "bidirectional"))
      (node (ref "IC7") (pin "114") (pinfunction "VDD_SOC_IN_6_114") (pintype "bidirectional"))
      (node (ref "IC7") (pin "134") (pinfunction "VDD_SOC_IN_7_134") (pintype "bidirectional"))
      (node (ref "IC7") (pin "31") (pinfunction "VDD_SOC_IN_2_31") (pintype "bidirectional"))
      (node (ref "IC7") (pin "39") (pinfunction "VDD_SOC_IN_3_39") (pintype "bidirectional"))
      (node (ref "IC7") (pin "5") (pinfunction "VDD_SOC_IN_1_5") (pintype "bidirectional"))
      (node (ref "IC7") (pin "86") (pinfunction "VDD_SOC_IN_4_86") (pintype "bidirectional"))
      (node (ref "L2") (pin "1") (pinfunction "1_1") (pintype "bidirectional"))
    )
    (net (code "7") (name "/DTR") (class "Default")
      (node (ref "H1") (pin "5") (pinfunction "5_5") (pintype "passive"))
      (node (ref "IC7") (pin "26") (pinfunction "GPIO_SD_B1_05_26") (pintype "bidirectional"))
    )
    (net (code "8") (name "/FLASH_3V3") (class "Default")
      (node (ref "C32") (pin "2") (pinfunction "2_2") (pintype "passive"))
      (node (ref "C5") (pin "2") (pinfunction "2_2") (pintype "passive"))
      (node (ref "IC10") (pin "8") (pinfunction "VCC_8") (pintype "bidirectional"))
      (node (ref "R1") (pin "1") (pinfunction "1_1") (pintype "passive"))
      (node (ref "R4") (pin "2") (pinfunction "2_2") (pintype "passive"))
    )
    (net (code "9") (name "/FLEXSPI_CLK") (class "Default")
      (node (ref "IC10") (pin "6") (pinfunction "SCK_6") (pintype "bidirectional"))
      (node (ref "IC7") (pin "24") (pinfunction "GPIO_SD_B1_07_24") (pintype "bidirectional"))
    )
    (net (code "10") (name "/FLEXSPI_D0_A") (class "Default")
      (node (ref "IC10") (pin "5") (pinfunction "SI_(IO0)_5") (pintype "bidirectional"))
      (node (ref "IC7") (pin "23") (pinfunction "GPIO_SD_B1_08_23") (pintype "bidirectional"))
    )
    (net (code "11") (name "/FLEXSPI_D1_A") (class "Default")
      (node (ref "IC10") (pin "2") (pinfunction "SO_(IO1)_2") (pintype "bidirectional"))
      (node (ref "IC7") (pin "21") (pinfunction "GPIO_SD_B1_10_21") (pintype "bidirectional"))
    )
    (net (code "12") (name "/FLEXSPI_D2_A") (class "Default")
      (node (ref "IC10") (pin "3") (pinfunction "WP#_(IO2)_3") (pintype "bidirectional"))
      (node (ref "IC7") (pin "22") (pinfunction "GPIO_SD_B1_09_22") (pintype "bidirectional"))
    )
    (net (code "13") (name "/FLEXSPI_D3_A") (class "Default")
      (node (ref "IC10") (pin "7") (pinfunction "HOLD#_(IO3)_7") (pintype "bidirectional"))
      (node (ref "IC7") (pin "25") (pinfunction "GPIO_SD_B1_06_25") (pintype "bidirectional"))
    )
    (net (code "14") (name "/FLEXSPI_SS0") (class "Default")
      (node (ref "IC10") (pin "1") (pinfunction "CE#_1") (pintype "bidirectional"))
      (node (ref "IC7") (pin "19") (pinfunction "GPIO_SD_B1_11_19") (pintype "bidirectional"))
      (node (ref "R1") (pin "2") (pinfunction "2_2") (pintype "passive"))
    )
    (net (code "15") (name "/GPANAIO") (class "Default")
      (node (ref "IC7") (pin "71") (pinfunction "GPANAIO_71") (pintype "bidirectional"))
      (node (ref "TP7") (pin "TP") (pinfunction "TP_TP") (pintype "input"))
    )
    (net (code "16") (name "/GPIO_EMC_16") (class "Default")
      (node (ref "IC9") (pin "23") (pinfunction "A0_23") (pintype "bidirectional"))
      (node (ref "R49") (pin "1") (pinfunction "1_1") (pintype "passive"))
    )
    (net (code "17") (name "/GPIO_EMC_17") (class "Default")
      (node (ref "IC9") (pin "24") (pinfunction "A1_24") (pintype "bidirectional"))
      (node (ref "R50") (pin "1") (pinfunction "1_1") (pintype "passive"))
    )
    (net (code "18") (name "/GPIO_EMC_18") (class "Default")
      (node (ref "IC9") (pin "25") (pinfunction "A2_25") (pintype "bidirectional"))
      (node (ref "R51") (pin "1") (pinfunction "1_1") (pintype "passive"))
    )
    (net (code "19") (name "/GPIO_EMC_19") (class "Default")
      (node (ref "IC9") (pin "26") (pinfunction "A3_26") (pintype "bidirectional"))
      (node (ref "R52") (pin "1") (pinfunction "1_1") (pintype "passive"))
    )
    (net (code "20") (name "/GPIO_EMC_20") (class "Default")
      (node (ref "IC9") (pin "29") (pinfunction "A4_29") (pintype "bidirectional"))
      (node (ref "R32") (pin "2") (pinfunction "2_2") (pintype "passive"))
    )
    (net (code "21") (name "/GPIO_EMC_21") (class "Default")
      (node (ref "IC9") (pin "30") (pinfunction "A5_30") (pintype "bidirectional"))
      (node (ref "R31") (pin "2") (pinfunction "2_2") (pintype "passive"))
    )
    (net (code "22") (name "/GPIO_EMC_22") (class "Default")
      (node (ref "IC9") (pin "31") (pinfunction "A6_31") (pintype "bidirectional"))
      (node (ref "R30") (pin "2") (pinfunction "2_2") (pintype "passive"))
    )
    (net (code "23") (name "/GPIO_EMC_23") (class "Default")
      (node (ref "IC9") (pin "32") (pinfunction "A7_32") (pintype "bidirectional"))
      (node (ref "R29") (pin "2") (pinfunction "2_2") (pintype "passive"))
    )
    (net (code "24") (name "/GPIO_EMC_24") (class "Default")
      (node (ref "IC9") (pin "33") (pinfunction "A8_33") (pintype "bidirectional"))
      (node (ref "R28") (pin "2") (pinfunction "2_2") (pintype "passive"))
    )
    (net (code "25") (name "/GPIO_EMC_25") (class "Default")
      (node (ref "IC9") (pin "34") (pinfunction "A9_34") (pintype "bidirectional"))
      (node (ref "R25") (pin "2") (pinfunction "2_2") (pintype "passive"))
    )
    (net (code "26") (name "/GPIO_EMC_26") (class "Default")
      (node (ref "IC9") (pin "35") (pinfunction "A11_35") (pintype "bidirectional"))
      (node (ref "R24") (pin "2") (pinfunction "2_2") (pintype "passive"))
    )
    (net (code "27") (name "/GPIO_EMC_27") (class "Default")
      (node (ref "IC9") (pin "36") (pinfunction "A12_36") (pintype "bidirectional"))
      (node (ref "R23") (pin "2") (pinfunction "2_2") (pintype "passive"))
    )
    (net (code "28") (name "/I2C1_SCL") (class "Default")
      (node (ref "H1") (pin "44") (pinfunction "44_44") (pintype "passive"))
      (node (ref "IC7") (pin "75") (pinfunction "GPIO_AD_B1_14_75") (pintype "bidirectional"))
    )
    (net (code "29") (name "/I2C1_SDA") (class "Default")
      (node (ref "H1") (pin "42") (pinfunction "42_42") (pintype "passive"))
      (node (ref "IC7") (pin "74") (pinfunction "GPIO_AD_B1_15_74") (pintype "bidirectional"))
    )
    (net (code "30") (name "/I2C2_SCL") (class "Default")
      (node (ref "H1") (pin "37") (pinfunction "37_37") (pintype "passive"))
      (node (ref "IC7") (pin "82") (pinfunction "GPIO_AD_B1_08_82") (pintype "bidirectional"))
    )
    (net (code "31") (name "/I2C2_SDA") (class "Default")
      (node (ref "H1") (pin "35") (pinfunction "35_35") (pintype "passive"))
      (node (ref "IC7") (pin "81") (pinfunction "GPIO_AD_B1_09_81") (pintype "bidirectional"))
    )
    (net (code "32") (name "/I2C3_SCL") (class "Default")
      (node (ref "H1") (pin "51") (pinfunction "51_51") (pintype "passive"))
      (node (ref "IC7") (pin "100") (pinfunction "GPIO_AD_B0_08_100") (pintype "bidirectional"))
    )
    (net (code "33") (name "/I2C3_SDA") (class "Default")
      (node (ref "H1") (pin "49") (pinfunction "49_49") (pintype "passive"))
      (node (ref "IC7") (pin "99") (pinfunction "GPIO_AD_B0_09_99") (pintype "bidirectional"))
    )
    (net (code "34") (name "/INT1_COMBO") (class "Default")
      (node (ref "IC7") (pin "27") (pinfunction "GPIO_SD_B1_04_27") (pintype "bidirectional"))
      (node (ref "R7") (pin "1") (pinfunction "1_1") (pintype "passive"))
    )
    (net (code "35") (name "/JTAG_DACK") (class "Default")
      (node (ref "J2") (pin "13") (pinfunction "13_13") (pintype "bidirectional"))
      (node (ref "R26") (pin "1") (pinfunction "1_1") (pintype "passive"))
    )
    (net (code "36") (name "/JTAG_DE") (class "Default")
      (node (ref "J2") (pin "6") (pinfunction "6_6") (pintype "bidirectional"))
    )
    (net (code "37") (name "/JTAG_MOD") (class "Default")
      (node (ref "IC7") (pin "109") (pinfunction "GPIO_AD_B0_02_109") (pintype "bidirectional"))
      (node (ref "R2") (pin "2") (pinfunction "2_2") (pintype "passive"))
    )
    (net (code "38") (name "/JTAG_NSRST") (class "Default")
      (node (ref "D2") (pin "1") (pinfunction "K_1") (pintype "bidirectional"))
      (node (ref "J2") (pin "12") (pinfunction "12_12") (pintype "bidirectional"))
    )
    (net (code "39") (name "/JTAG_NTRST") (class "Default")
      (node (ref "IC7") (pin "106") (pinfunction "GPIO_AD_B0_05_106") (pintype "bidirectional"))
      (node (ref "J2") (pin "9") (pinfunction "9_9") (pintype "bidirectional"))
      (node (ref "R63") (pin "2") (pinfunction "2_2") (pintype "passive"))
    )
    (net (code "40") (name "/JTAG_RTCK") (class "Default")
      (node (ref "J2") (pin "11") (pinfunction "11_11") (pintype "bidirectional"))
    )
    (net (code "41") (name "/JTAG_TCK") (class "Default")
      (node (ref "IC7") (pin "110") (pinfunction "GPIO_AD_B0_01_110") (pintype "bidirectional"))
      (node (ref "J2") (pin "4") (pinfunction "4_4") (pintype "bidirectional"))
    )
    (net (code "42") (name "/JTAG_TDI") (class "Default")
      (node (ref "IC7") (pin "108") (pinfunction "GPIO_AD_B0_03_108") (pintype "bidirectional"))
      (node (ref "J2") (pin "3") (pinfunction "3_3") (pintype "bidirectional"))
    )
    (net (code "43") (name "/JTAG_TDO") (class "Default")
      (node (ref "IC7") (pin "107") (pinfunction "GPIO_AD_B0_04_107") (pintype "bidirectional"))
      (node (ref "J2") (pin "5") (pinfunction "5_5") (pintype "bidirectional"))
    )
    (net (code "44") (name "/JTAG_TMS") (class "Default")
      (node (ref "IC7") (pin "111") (pinfunction "GPIO_AD_B0_00_111") (pintype "bidirectional"))
      (node (ref "J2") (pin "10") (pinfunction "10_10") (pintype "bidirectional"))
    )
    (net (code "45") (name "/NVCC_GPIO_3V3") (class "Default")
      (node (ref "C53") (pin "2") (pinfunction "2_2") (pintype "passive"))
      (node (ref "C54") (pin "2") (pinfunction "2_2") (pintype "passive"))
      (node (ref "C55") (pin "2") (pinfunction "2_2") (pintype "passive"))
      (node (ref "C56") (pin "2") (pinfunction "2_2") (pintype "passive"))
      (node (ref "C57") (pin "2") (pinfunction "2_2") (pintype "passive"))
      (node (ref "C58") (pin "2") (pinfunction "2_2") (pintype "passive"))
      (node (ref "C59") (pin "2") (pinfunction "2_2") (pintype "passive"))
      (node (ref "C60") (pin "2") (pinfunction "2_2") (pintype "passive"))
      (node (ref "C61") (pin "2") (pinfunction "2_2") (pintype "passive"))
      (node (ref "C62") (pin "2") (pinfunction "2_2") (pintype "passive"))
      (node (ref "C63") (pin "2") (pinfunction "2_2") (pintype "passive"))
      (node (ref "C64") (pin "2") (pinfunction "2_2") (pintype "passive"))
      (node (ref "IC7") (pin "104") (pinfunction "NVCC_GPIO_5_104") (pintype "bidirectional"))
      (node (ref "IC7") (pin "11") (pinfunction "NVCC_GPIO_1_11") (pintype "bidirectional"))
      (node (ref "IC7") (pin "112") (pinfunction "NVCC_GPIO_6_112") (pintype "bidirectional"))
      (node (ref "IC7") (pin "144") (pinfunction "NVCC_GPIO_7_144") (pintype "bidirectional"))
      (node (ref "IC7") (pin "20") (pinfunction "NVCC_GPIO_2_20") (pintype "bidirectional"))
      (node (ref "IC7") (pin "29") (pinfunction "NVCC_GPIO_3_29") (pintype "bidirectional"))
      (node (ref "IC7") (pin "77") (pinfunction "NVCC_GPIO_4_77") (pintype "bidirectional"))
      (node (ref "R62") (pin "1") (pinfunction "1_1") (pintype "passive"))
    )
    (net (code "46") (name "/NVCC_PLL") (class "Default")
      (node (ref "C22") (pin "2") (pinfunction "2_2") (pintype "passive"))
      (node (ref "IC7") (pin "72") (pinfunction "NVCC_PLL_72") (pintype "bidirectional"))
    )
    (net (code "47") (name "/NVCC_SD0") (class "Default")
      (node (ref "C1") (pin "2") (pinfunction "2_2") (pintype "passive"))
      (node (ref "C2") (pin "2") (pinfunction "2_2") (pintype "passive"))
      (node (ref "IC7") (pin "44") (pinfunction "NVCC_SD0_44") (pintype "bidirectional"))
      (node (ref "R3") (pin "2") (pinfunction "2_2") (pintype "passive"))
    )
    (net (code "48") (name "/PMIC_STBY_REQ") (class "Default")
      (node (ref "IC7") (pin "54") (pinfunction "PMIC_STBY_REQ_54") (pintype "bidirectional"))
      (node (ref "TP6") (pin "TP") (pinfunction "TP_TP") (pintype "input"))
    )
    (net (code "49") (name "/POR_B") (class "Default")
      (node (ref "C36") (pin "2") (pinfunction "2_2") (pintype "passive"))
      (node (ref "D2") (pin "2") (pinfunction "A_2") (pintype "bidirectional"))
      (node (ref "D4") (pin "1") (pinfunction "K_1") (pintype "bidirectional"))
      (node (ref "IC7") (pin "50") (pinfunction "POR_B_50") (pintype "bidirectional"))
      (node (ref "R8") (pin "2") (pinfunction "2_2") (pintype "passive"))
    )
    (net (code "50") (name "/RTC_XTALI") (class "Default")
      (node (ref "C41") (pin "2") (pinfunction "2_2") (pintype "passive"))
      (node (ref "IC7") (pin "57") (pinfunction "RTC_XTALI_57") (pintype "bidirectional"))
      (node (ref "Y2") (pin "1") (pinfunction "IN/OUT_1") (pintype "bidirectional"))
    )
    (net (code "51") (name "/RTC_XTALO") (class "Default")
      (node (ref "C42") (pin "2") (pinfunction "2_2") (pintype "passive"))
      (node (ref "IC7") (pin "58") (pinfunction "RTC_XTALO_58") (pintype "bidirectional"))
      (node (ref "Y2") (pin "2") (pinfunction "OUT/IN_2") (pintype "bidirectional"))
    )
    (net (code "52") (name "/SD1_CLK") (class "Default")
      (node (ref "IC7") (pin "45") (pinfunction "GPIO_SD_B0_03_45") (pintype "bidirectional"))
      (node (ref "R56") (pin "1") (pinfunction "1_1") (pintype "passive"))
    )
    (net (code "53") (name "/SD1_CMD") (class "Default")
      (node (ref "IC7") (pin "46") (pinfunction "GPIO_SD_B0_02_46") (pintype "bidirectional"))
      (node (ref "R5") (pin "2") (pinfunction "2_2") (pintype "passive"))
      (node (ref "R55") (pin "1") (pinfunction "1_1") (pintype "passive"))
    )
    (net (code "54") (name "/SD1_D0") (class "Default")
      (node (ref "IC7") (pin "43") (pinfunction "GPIO_SD_B0_04_43") (pintype "bidirectional"))
      (node (ref "R57") (pin "1") (pinfunction "1_1") (pintype "passive"))
      (node (ref "R6") (pin "2") (pinfunction "2_2") (pintype "passive"))
    )
    (net (code "55") (name "/SD1_D1") (class "Default")
      (node (ref "IC7") (pin "42") (pinfunction "GPIO_SD_B0_05_42") (pintype "bidirectional"))
      (node (ref "R58") (pin "1") (pinfunction "1_1") (pintype "passive"))
    )
    (net (code "56") (name "/SD1_D2") (class "Default")
      (node (ref "IC7") (pin "48") (pinfunction "GPIO_SD_B0_00_48") (pintype "bidirectional"))
      (node (ref "R53") (pin "1") (pinfunction "1_1") (pintype "passive"))
    )
    (net (code "57") (name "/SD1_D3") (class "Default")
      (node (ref "IC7") (pin "47") (pinfunction "GPIO_SD_B0_01_47") (pintype "bidirectional"))
      (node (ref "R54") (pin "1") (pinfunction "1_1") (pintype "passive"))
    )
    (net (code "58") (name "/SDRAM_3V3") (class "Default")
      (node (ref "C10") (pin "1") (pinfunction "1_1") (pintype "passive"))
      (node (ref "C11") (pin "1") (pinfunction "1_1") (pintype "passive"))
      (node (ref "C12") (pin "1") (pinfunction "1_1") (pintype "passive"))
      (node (ref "C13") (pin "1") (pinfunction "1_1") (pintype "passive"))
      (node (ref "C6") (pin "1") (pinfunction "1_1") (pintype "passive"))
      (node (ref "C7") (pin "1") (pinfunction "1_1") (pintype "passive"))
      (node (ref "C8") (pin "1") (pinfunction "1_1") (pintype "passive"))
      (node (ref "C9") (pin "1") (pinfunction "1_1") (pintype "passive"))
      (node (ref "FB1") (pin "2") (pinfunction "2_2") (pintype "bidirectional"))
      (node (ref "IC9") (pin "1") (pinfunction "VDD_1_1") (pintype "bidirectional"))
      (node (ref "IC9") (pin "14") (pinfunction "VDD_2_14") (pintype "bidirectional"))
      (node (ref "IC9") (pin "27") (pinfunction "VDD_3_27") (pintype "bidirectional"))
      (node (ref "IC9") (pin "3") (pinfunction "VDDQ_1_3") (pintype "bidirectional"))
      (node (ref "IC9") (pin "43") (pinfunction "VDDQ_3_43") (pintype "bidirectional"))
      (node (ref "IC9") (pin "49") (pinfunction "VDDQ_4_49") (pintype "bidirectional"))
      (node (ref "IC9") (pin "9") (pinfunction "VDDQ_2_9") (pintype "bidirectional"))
    )
    (net (code "59") (name "/SD_CD_SW") (class "Default")
      (node (ref "IC7") (pin "41") (pinfunction "GPIO_SD_B0_06_41") (pintype "bidirectional"))
      (node (ref "J1") (pin "9") (pinfunction "9_9") (pintype "bidirectional"))
      (node (ref "R59") (pin "1") (pinfunction "1_1") (pintype "passive"))
    )
    (net (code "60") (name "/SD_PWREN") (class "Default")
      (node (ref "D3") (pin "1") (pinfunction "K_1") (pintype "bidirectional"))
      (node (ref "R7") (pin "2") (pinfunction "2_2") (pintype "passive"))
    )
    (net (code "61") (name "/SEMC_A0") (class "Default")
      (node (ref "IC7") (pin "142") (pinfunction "GPIO_EMC_16_142") (pintype "bidirectional"))
      (node (ref "R49") (pin "2") (pinfunction "2_2") (pintype "passive"))
    )
    (net (code "62") (name "/SEMC_A1") (class "Default")
      (node (ref "IC7") (pin "141") (pinfunction "GPIO_EMC_17_141") (pintype "bidirectional"))
      (node (ref "R50") (pin "2") (pinfunction "2_2") (pintype "passive"))
    )
    (net (code "63") (name "/SEMC_A2") (class "Default")
      (node (ref "IC7") (pin "140") (pinfunction "GPIO_EMC_18_140") (pintype "bidirectional"))
      (node (ref "R51") (pin "2") (pinfunction "2_2") (pintype "passive"))
    )
    (net (code "64") (name "/SEMC_A3") (class "Default")
      (node (ref "IC7") (pin "139") (pinfunction "GPIO_EMC_19_139") (pintype "bidirectional"))
      (node (ref "R52") (pin "2") (pinfunction "2_2") (pintype "passive"))
    )
    (net (code "65") (name "/SEMC_A4") (class "Default")
      (node (ref "IC7") (pin "138") (pinfunction "GPIO_EMC_20_138") (pintype "bidirectional"))
      (node (ref "R32") (pin "1") (pinfunction "1_1") (pintype "passive"))
    )
    (net (code "66") (name "/SEMC_A5") (class "Default")
      (node (ref "IC7") (pin "137") (pinfunction "GPIO_EMC_21_137") (pintype "bidirectional"))
      (node (ref "R31") (pin "1") (pinfunction "1_1") (pintype "passive"))
    )
    (net (code "67") (name "/SEMC_A6") (class "Default")
      (node (ref "IC7") (pin "136") (pinfunction "GPIO_EMC_22_136") (pintype "bidirectional"))
      (node (ref "R30") (pin "1") (pinfunction "1_1") (pintype "passive"))
    )
    (net (code "68") (name "/SEMC_A7") (class "Default")
      (node (ref "IC7") (pin "133") (pinfunction "GPIO_EMC_23_133") (pintype "bidirectional"))
      (node (ref "R29") (pin "1") (pinfunction "1_1") (pintype "passive"))
    )
    (net (code "69") (name "/SEMC_A8") (class "Default")
      (node (ref "IC7") (pin "132") (pinfunction "GPIO_EMC_24_132") (pintype "bidirectional"))
      (node (ref "R28") (pin "1") (pinfunction "1_1") (pintype "passive"))
    )
    (net (code "70") (name "/SEMC_A9") (class "Default")
      (node (ref "IC7") (pin "131") (pinfunction "GPIO_EMC_25_131") (pintype "bidirectional"))
      (node (ref "R25") (pin "1") (pinfunction "1_1") (pintype "passive"))
    )
    (net (code "71") (name "/SEMC_A10") (class "Default")
      (node (ref "IC7") (pin "143") (pinfunction "GPIO_EMC_15_143") (pintype "bidirectional"))
      (node (ref "R48") (pin "2") (pinfunction "2_2") (pintype "passive"))
    )
    (net (code "72") (name "/SEMC_A11") (class "Default")
      (node (ref "IC7") (pin "130") (pinfunction "GPIO_EMC_26_130") (pintype "bidirectional"))
      (node (ref "R24") (pin "1") (pinfunction "1_1") (pintype "passive"))
    )
    (net (code "73") (name "/SEMC_A12") (class "Default")
      (node (ref "IC7") (pin "129") (pinfunction "GPIO_EMC_27_129") (pintype "bidirectional"))
      (node (ref "R23") (pin "1") (pinfunction "1_1") (pintype "passive"))
    )
    (net (code "74") (name "/SEMC_BA0") (class "Default")
      (node (ref "IC7") (pin "2") (pinfunction "GPIO_EMC_13_2") (pintype "bidirectional"))
      (node (ref "R46") (pin "2") (pinfunction "2_2") (pintype "passive"))
    )
    (net (code "75") (name "/SEMC_BA1") (class "Default")
      (node (ref "IC7") (pin "1") (pinfunction "GPIO_EMC_14_1") (pintype "bidirectional"))
      (node (ref "R47") (pin "2") (pinfunction "2_2") (pintype "passive"))
    )
    (net (code "76") (name "/SEMC_CAS") (class "Default")
      (node (ref "IC7") (pin "7") (pinfunction "GPIO_EMC_10_7") (pintype "bidirectional"))
      (node (ref "R43") (pin "2") (pinfunction "2_2") (pintype "passive"))
    )
    (net (code "77") (name "/SEMC_CKE") (class "Default")
      (node (ref "IC7") (pin "127") (pinfunction "GPIO_EMC_29_127") (pintype "bidirectional"))
      (node (ref "R22") (pin "1") (pinfunction "1_1") (pintype "passive"))
    )
    (net (code "78") (name "/SEMC_CLK") (class "Default")
      (node (ref "IC7") (pin "126") (pinfunction "GPIO_EMC_30_126") (pintype "bidirectional"))
      (node (ref "R21") (pin "1") (pinfunction "1_1") (pintype "passive"))
    )
    (net (code "79") (name "/SEMC_CS0") (class "Default")
      (node (ref "IC7") (pin "3") (pinfunction "GPIO_EMC_12_3") (pintype "bidirectional"))
      (node (ref "R45") (pin "2") (pinfunction "2_2") (pintype "passive"))
    )
    (net (code "80") (name "/SEMC_D0") (class "Default")
      (node (ref "IC7") (pin "18") (pinfunction "GPIO_EMC_00_18") (pintype "bidirectional"))
      (node (ref "R33") (pin "2") (pinfunction "2_2") (pintype "passive"))
    )
    (net (code "81") (name "/SEMC_D1") (class "Default")
      (node (ref "IC7") (pin "17") (pinfunction "GPIO_EMC_01_17") (pintype "bidirectional"))
      (node (ref "R34") (pin "2") (pinfunction "2_2") (pintype "passive"))
    )
    (net (code "82") (name "/SEMC_D2") (class "Default")
      (node (ref "IC7") (pin "16") (pinfunction "GPIO_EMC_02_16") (pintype "bidirectional"))
      (node (ref "R35") (pin "2") (pinfunction "2_2") (pintype "passive"))
    )
    (net (code "83") (name "/SEMC_D3") (class "Default")
      (node (ref "IC7") (pin "15") (pinfunction "GPIO_EMC_03_15") (pintype "bidirectional"))
      (node (ref "R36") (pin "2") (pinfunction "2_2") (pintype "passive"))
    )
    (net (code "84") (name "/SEMC_D4") (class "Default")
      (node (ref "IC7") (pin "14") (pinfunction "GPIO_EMC_04_14") (pintype "bidirectional"))
      (node (ref "R37") (pin "2") (pinfunction "2_2") (pintype "passive"))
    )
    (net (code "85") (name "/SEMC_D5") (class "Default")
      (node (ref "IC7") (pin "13") (pinfunction "GPIO_EMC_05_13") (pintype "bidirectional"))
      (node (ref "R38") (pin "2") (pinfunction "2_2") (pintype "passive"))
    )
    (net (code "86") (name "/SEMC_D6") (class "Default")
      (node (ref "IC7") (pin "12") (pinfunction "GPIO_EMC_06_12") (pintype "bidirectional"))
      (node (ref "R39") (pin "2") (pinfunction "2_2") (pintype "passive"))
    )
    (net (code "87") (name "/SEMC_D7") (class "Default")
      (node (ref "IC7") (pin "10") (pinfunction "GPIO_EMC_07_10") (pintype "bidirectional"))
      (node (ref "R40") (pin "2") (pinfunction "2_2") (pintype "passive"))
    )
    (net (code "88") (name "/SEMC_D8") (class "Default")
      (node (ref "IC7") (pin "124") (pinfunction "GPIO_EMC_32_124") (pintype "bidirectional"))
      (node (ref "R19") (pin "1") (pinfunction "1_1") (pintype "passive"))
    )
    (net (code "89") (name "/SEMC_D9") (class "Default")
      (node (ref "IC7") (pin "123") (pinfunction "GPIO_EMC_33_123") (pintype "bidirectional"))
      (node (ref "R18") (pin "1") (pinfunction "1_1") (pintype "passive"))
    )
    (net (code "90") (name "/SEMC_D10") (class "Default")
      (node (ref "IC7") (pin "122") (pinfunction "GPIO_EMC_34_122") (pintype "bidirectional"))
      (node (ref "R17") (pin "1") (pinfunction "1_1") (pintype "passive"))
    )
    (net (code "91") (name "/SEMC_D11") (class "Default")
      (node (ref "IC7") (pin "121") (pinfunction "GPIO_EMC_35_121") (pintype "bidirectional"))
      (node (ref "R16") (pin "1") (pinfunction "1_1") (pintype "passive"))
    )
    (net (code "92") (name "/SEMC_D12") (class "Default")
      (node (ref "IC7") (pin "120") (pinfunction "GPIO_EMC_36_120") (pintype "bidirectional"))
      (node (ref "R15") (pin "1") (pinfunction "1_1") (pintype "passive"))
    )
    (net (code "93") (name "/SEMC_D13") (class "Default")
      (node (ref "IC7") (pin "119") (pinfunction "GPIO_EMC_37_119") (pintype "bidirectional"))
      (node (ref "R14") (pin "1") (pinfunction "1_1") (pintype "passive"))
    )
    (net (code "94") (name "/SEMC_D14") (class "Default")
      (node (ref "IC7") (pin "118") (pinfunction "GPIO_EMC_38_118") (pintype "bidirectional"))
      (node (ref "R13") (pin "1") (pinfunction "1_1") (pintype "passive"))
    )
    (net (code "95") (name "/SEMC_D15") (class "Default")
      (node (ref "IC7") (pin "117") (pinfunction "GPIO_EMC_39_117") (pintype "bidirectional"))
      (node (ref "R12") (pin "1") (pinfunction "1_1") (pintype "passive"))
    )
    (net (code "96") (name "/SEMC_DM0") (class "Default")
      (node (ref "IC7") (pin "9") (pinfunction "GPIO_EMC_08_9") (pintype "bidirectional"))
      (node (ref "R41") (pin "2") (pinfunction "2_2") (pintype "passive"))
    )
    (net (code "97") (name "/SEMC_DM1") (class "Default")
      (node (ref "IC7") (pin "125") (pinfunction "GPIO_EMC_31_125") (pintype "bidirectional"))
      (node (ref "R20") (pin "1") (pinfunction "1_1") (pintype "passive"))
    )
    (net (code "98") (name "/SEMC_RAS") (class "Default")
      (node (ref "IC7") (pin "4") (pinfunction "GPIO_EMC_11_4") (pintype "bidirectional"))
      (node (ref "R44") (pin "2") (pinfunction "2_2") (pintype "passive"))
    )
    (net (code "99") (name "/SEMC_WE") (class "Default")
      (node (ref "IC7") (pin "8") (pinfunction "GPIO_EMC_09_8") (pintype "bidirectional"))
      (node (ref "R42") (pin "2") (pinfunction "2_2") (pintype "passive"))
    )
    (net (code "100") (name "/SPI1_EN0") (class "Default")
      (node (ref "H1") (pin "9") (pinfunction "9_9") (pintype "passive"))
      (node (ref "IC7") (pin "92") (pinfunction "GPIO_AD_B1_00_92") (pintype "bidirectional"))
    )
    (net (code "101") (name "/SPI1_EN1") (class "Default")
      (node (ref "H1") (pin "10") (pinfunction "10_10") (pintype "passive"))
      (node (ref "IC7") (pin "91") (pinfunction "GPIO_AD_B1_01_91") (pintype "bidirectional"))
    )
    (net (code "102") (name "/SPI1_EN2") (class "Default")
      (node (ref "H1") (pin "22") (pinfunction "22_22") (pintype "passive"))
      (node (ref "IC7") (pin "90") (pinfunction "GPIO_AD_B1_02_90") (pintype "bidirectional"))
    )
    (net (code "103") (name "/SPI1_EN3") (class "Default")
      (node (ref "H1") (pin "21") (pinfunction "21_21") (pintype "passive"))
      (node (ref "IC7") (pin "89") (pinfunction "GPIO_AD_B1_03_89") (pintype "bidirectional"))
    )
    (net (code "104") (name "/SPI1_MISO") (class "Default")
      (node (ref "H1") (pin "18") (pinfunction "18_18") (pintype "passive"))
      (node (ref "IC7") (pin "95") (pinfunction "GPIO_AD_B0_13_95") (pintype "bidirectional"))
    )
    (net (code "105") (name "/SPI1_MOSI") (class "Default")
      (node (ref "H1") (pin "16") (pinfunction "16_16") (pintype "passive"))
      (node (ref "IC7") (pin "96") (pinfunction "GPIO_AD_B0_12_96") (pintype "bidirectional"))
    )
    (net (code "106") (name "/SPI1_PCS0") (class "Default")
      (node (ref "H1") (pin "7") (pinfunction "7_7") (pintype "passive"))
      (node (ref "IC7") (pin "97") (pinfunction "GPIO_AD_B0_11_97") (pintype "bidirectional"))
    )
    (net (code "107") (name "/SPI1_PCS1") (class "Default")
      (node (ref "H1") (pin "8") (pinfunction "8_8") (pintype "passive"))
      (node (ref "IC7") (pin "88") (pinfunction "GPIO_AD_B1_04_88") (pintype "bidirectional"))
    )
    (net (code "108") (name "/SPI1_PCS2") (class "Default")
      (node (ref "H1") (pin "20") (pinfunction "20_20") (pintype "passive"))
      (node (ref "IC7") (pin "87") (pinfunction "GPIO_AD_B1_05_87") (pintype "bidirectional"))
    )
    (net (code "109") (name "/SPI1_PCS3") (class "Default")
      (node (ref "H1") (pin "19") (pinfunction "19_19") (pintype "passive"))
      (node (ref "IC7") (pin "84") (pinfunction "GPIO_AD_B1_06_84") (pintype "bidirectional"))
    )
    (net (code "110") (name "/SPI1_SCK") (class "Default")
      (node (ref "H1") (pin "12") (pinfunction "12_12") (pintype "passive"))
      (node (ref "IC7") (pin "98") (pinfunction "GPIO_AD_B0_10_98") (pintype "bidirectional"))
    )
    (net (code "111") (name "/UART1_RX") (class "Default")
      (node (ref "H1") (pin "4") (pinfunction "4_4") (pintype "passive"))
      (node (ref "IC7") (pin "101") (pinfunction "GPIO_AD_B0_07_101") (pintype "bidirectional"))
    )
    (net (code "112") (name "/UART1_TX") (class "Default")
      (node (ref "H1") (pin "2") (pinfunction "2_2") (pintype "passive"))
      (node (ref "IC7") (pin "105") (pinfunction "GPIO_AD_B0_06_105") (pintype "bidirectional"))
    )
    (net (code "113") (name "/UART3_RX") (class "Default")
      (node (ref "H1") (pin "52") (pinfunction "52_52") (pintype "passive"))
      (node (ref "IC7") (pin "93") (pinfunction "GPIO_AD_B0_15_93") (pintype "bidirectional"))
    )
    (net (code "114") (name "/UART3_TX") (class "Default")
      (node (ref "H1") (pin "50") (pinfunction "50_50") (pintype "passive"))
      (node (ref "IC7") (pin "94") (pinfunction "GPIO_AD_B0_14_94") (pintype "bidirectional"))
    )
    (net (code "115") (name "/UART4_RX") (class "Default")
      (node (ref "H1") (pin "3") (pinfunction "3_3") (pintype "passive"))
      (node (ref "IC7") (pin "79") (pinfunction "GPIO_AD_B1_11_79") (pintype "bidirectional"))
    )
    (net (code "116") (name "/UART4_TX") (class "Default")
      (node (ref "H1") (pin "1") (pinfunction "1_1") (pintype "passive"))
      (node (ref "IC7") (pin "80") (pinfunction "GPIO_AD_B1_10_80") (pintype "bidirectional"))
    )
    (net (code "117") (name "/USB_OTG1_CHD") (class "Default")
      (node (ref "IC7") (pin "66") (pinfunction "USB_OTG1_CHD_B_66") (pintype "bidirectional"))
      (node (ref "TP5") (pin "TP") (pinfunction "TP_TP") (pintype "input"))
    )
    (net (code "118") (name "/USER_LED") (class "Default")
      (node (ref "D11") (pin "1") (pinfunction "CATHODE_1") (pintype "passive"))
      (node (ref "R63") (pin "1") (pinfunction "1_1") (pintype "passive"))
    )
    (net (code "119") (name "/VDD_HIGH_CAP") (class "Default")
      (node (ref "C23") (pin "2") (pinfunction "2_2") (pintype "passive"))
      (node (ref "C24") (pin "2") (pinfunction "2_2") (pintype "passive"))
      (node (ref "IC7") (pin "65") (pinfunction "VDD_HIGH_CAP_65") (pintype "bidirectional"))
    )
    (net (code "120") (name "/VDD_SNVS_CAP") (class "Default")
      (node (ref "C21") (pin "2") (pinfunction "2_2") (pintype "passive"))
      (node (ref "IC7") (pin "56") (pinfunction "VDD_SNVS_CAP_56") (pintype "bidirectional"))
    )
    (net (code "121") (name "/VDD_USB_3V") (class "Default")
      (node (ref "C14") (pin "2") (pinfunction "2_2") (pintype "passive"))
      (node (ref "C4") (pin "2") (pinfunction "2_2") (pintype "passive"))
      (node (ref "IC7") (pin "61") (pinfunction "VDD_USB_CAP_61") (pintype "bidirectional"))
    )
    (net (code "122") (name "/VSD_3V3") (class "Default")
      (node (ref "C38") (pin "2") (pinfunction "2_2") (pintype "passive"))
      (node (ref "C49") (pin "2") (pinfunction "2_2") (pintype "passive"))
      (node (ref "C52") (pin "2") (pinfunction "2_2") (pintype "passive"))
      (node (ref "IC8") (pin "3") (pinfunction "VOUT_3") (pintype "bidirectional"))
      (node (ref "J1") (pin "4") (pinfunction "VDD_4") (pintype "power_in"))
    )
    (net (code "123") (name "/WAKEUP") (class "Default")
      (node (ref "IC7") (pin "52") (pinfunction "WAKEUP_52") (pintype "bidirectional"))
      (node (ref "TP8") (pin "TP") (pinfunction "TP_TP") (pintype "input"))
    )
    (net (code "124") (name "/XTALI") (class "Default")
      (node (ref "C39") (pin "2") (pinfunction "2_2") (pintype "passive"))
      (node (ref "IC7") (pin "67") (pinfunction "XTALI_67") (pintype "bidirectional"))
      (node (ref "R10") (pin "1") (pinfunction "1_1") (pintype "passive"))
      (node (ref "Y1") (pin "3") (pinfunction "XTAL_2_3") (pintype "bidirectional"))
    )
    (net (code "125") (name "/XTALO") (class "Default")
      (node (ref "C40") (pin "2") (pinfunction "2_2") (pintype "passive"))
      (node (ref "IC7") (pin "68") (pinfunction "XTALO_68") (pintype "bidirectional"))
      (node (ref "Y1") (pin "1") (pinfunction "XTAL_1_1") (pintype "bidirectional"))
    )
    (net (code "126") (name "GND") (class "Default")
      (node (ref "C1") (pin "1") (pinfunction "1_1") (pintype "passive"))
      (node (ref "C10") (pin "2") (pinfunction "2_2") (pintype "passive"))
      (node (ref "C11") (pin "2") (pinfunction "2_2") (pintype "passive"))
      (node (ref "C12") (pin "2") (pinfunction "2_2") (pintype "passive"))
      (node (ref "C13") (pin "2") (pinfunction "2_2") (pintype "passive"))
      (node (ref "C14") (pin "1") (pinfunction "1_1") (pintype "passive"))
      (node (ref "C15") (pin "1") (pinfunction "1_1") (pintype "passive"))
      (node (ref "C16") (pin "1") (pinfunction "1_1") (pintype "passive"))
      (node (ref "C17") (pin "1") (pinfunction "1_1") (pintype "passive"))
      (node (ref "C18") (pin "1") (pinfunction "1_1") (pintype "passive"))
      (node (ref "C19") (pin "1") (pinfunction "1_1") (pintype "passive"))
      (node (ref "C2") (pin "1") (pinfunction "1_1") (pintype "passive"))
      (node (ref "C20") (pin "1") (pinfunction "1_1") (pintype "passive"))
      (node (ref "C21") (pin "1") (pinfunction "1_1") (pintype "passive"))
      (node (ref "C22") (pin "1") (pinfunction "1_1") (pintype "passive"))
      (node (ref "C23") (pin "1") (pinfunction "1_1") (pintype "passive"))
      (node (ref "C24") (pin "1") (pinfunction "1_1") (pintype "passive"))
      (node (ref "C25") (pin "1") (pinfunction "1_1") (pintype "passive"))
      (node (ref "C26") (pin "1") (pinfunction "1_1") (pintype "passive"))
      (node (ref "C27") (pin "1") (pinfunction "1_1") (pintype "passive"))
      (node (ref "C28") (pin "1") (pinfunction "1_1") (pintype "passive"))
      (node (ref "C29") (pin "1") (pinfunction "1_1") (pintype "passive"))
      (node (ref "C3") (pin "1") (pinfunction "1_1") (pintype "passive"))
      (node (ref "C30") (pin "1") (pinfunction "1_1") (pintype "passive"))
      (node (ref "C31") (pin "1") (pinfunction "1_1") (pintype "passive"))
      (node (ref "C32") (pin "1") (pinfunction "1_1") (pintype "passive"))
      (node (ref "C33") (pin "1") (pinfunction "1_1") (pintype "passive"))
      (node (ref "C34") (pin "1") (pinfunction "1_1") (pintype "passive"))
      (node (ref "C35") (pin "1") (pinfunction "1_1") (pintype "passive"))
      (node (ref "C36") (pin "1") (pinfunction "1_1") (pintype "passive"))
      (node (ref "C37") (pin "1") (pinfunction "1_1") (pintype "passive"))
      (node (ref "C38") (pin "1") (pinfunction "1_1") (pintype "passive"))
      (node (ref "C39") (pin "1") (pinfunction "1_1") (pintype "passive"))
      (node (ref "C4") (pin "1") (pinfunction "1_1") (pintype "passive"))
      (node (ref "C40") (pin "1") (pinfunction "1_1") (pintype "passive"))
      (node (ref "C41") (pin "1") (pinfunction "1_1") (pintype "passive"))
      (node (ref "C42") (pin "1") (pinfunction "1_1") (pintype "passive"))
      (node (ref "C43") (pin "1") (pinfunction "1_1") (pintype "passive"))
      (node (ref "C44") (pin "1") (pinfunction "1_1") (pintype "passive"))
      (node (ref "C45") (pin "1") (pinfunction "1_1") (pintype "passive"))
      (node (ref "C46") (pin "1") (pinfunction "1_1") (pintype "passive"))
      (node (ref "C47") (pin "1") (pinfunction "1_1") (pintype "passive"))
      (node (ref "C48") (pin "1") (pinfunction "1_1") (pintype "passive"))
      (node (ref "C49") (pin "1") (pinfunction "1_1") (pintype "passive"))
      (node (ref "C5") (pin "1") (pinfunction "1_1") (pintype "passive"))
      (node (ref "C50") (pin "1") (pinfunction "1_1") (pintype "passive"))
      (node (ref "C51") (pin "1") (pinfunction "1_1") (pintype "passive"))
      (node (ref "C52") (pin "1") (pinfunction "1_1") (pintype "passive"))
      (node (ref "C53") (pin "1") (pinfunction "1_1") (pintype "passive"))
      (node (ref "C54") (pin "1") (pinfunction "1_1") (pintype "passive"))
      (node (ref "C55") (pin "1") (pinfunction "1_1") (pintype "passive"))
      (node (ref "C56") (pin "1") (pinfunction "1_1") (pintype "passive"))
      (node (ref "C57") (pin "1") (pinfunction "1_1") (pintype "passive"))
      (node (ref "C58") (pin "1") (pinfunction "1_1") (pintype "passive"))
      (node (ref "C59") (pin "1") (pinfunction "1_1") (pintype "passive"))
      (node (ref "C6") (pin "2") (pinfunction "2_2") (pintype "passive"))
      (node (ref "C60") (pin "1") (pinfunction "1_1") (pintype "passive"))
      (node (ref "C61") (pin "1") (pinfunction "1_1") (pintype "passive"))
      (node (ref "C62") (pin "1") (pinfunction "1_1") (pintype "passive"))
      (node (ref "C63") (pin "1") (pinfunction "1_1") (pintype "passive"))
      (node (ref "C64") (pin "1") (pinfunction "1_1") (pintype "passive"))
      (node (ref "C7") (pin "2") (pinfunction "2_2") (pintype "passive"))
      (node (ref "C8") (pin "2") (pinfunction "2_2") (pintype "passive"))
      (node (ref "C9") (pin "2") (pinfunction "2_2") (pintype "passive"))
      (node (ref "H2") (pin "10") (pinfunction "10_10") (pintype "passive"))
      (node (ref "H2") (pin "13") (pinfunction "13_13") (pintype "passive"))
      (node (ref "H2") (pin "18") (pinfunction "18_18") (pintype "passive"))
      (node (ref "H2") (pin "21") (pinfunction "21_21") (pintype "passive"))
      (node (ref "H2") (pin "22") (pinfunction "22_22") (pintype "passive"))
      (node (ref "H2") (pin "29") (pinfunction "29_29") (pintype "passive"))
      (node (ref "H2") (pin "30") (pinfunction "30_30") (pintype "passive"))
      (node (ref "H2") (pin "31") (pinfunction "31_31") (pintype "passive"))
      (node (ref "H2") (pin "47") (pinfunction "47_47") (pintype "passive"))
      (node (ref "H2") (pin "48") (pinfunction "48_48") (pintype "passive"))
      (node (ref "IC1") (pin "1") (pinfunction "GND_1") (pintype "bidirectional"))
      (node (ref "IC10") (pin "4") (pinfunction "GND_4") (pintype "bidirectional"))
      (node (ref "IC7") (pin "103") (pinfunction "VSS_6_103") (pintype "bidirectional"))
      (node (ref "IC7") (pin "113") (pinfunction "VSS_7_113") (pintype "bidirectional"))
      (node (ref "IC7") (pin "135") (pinfunction "VSS_8_135") (pintype "bidirectional"))
      (node (ref "IC7") (pin "35") (pinfunction "DCDC_GND_35") (pintype "bidirectional"))
      (node (ref "IC7") (pin "40") (pinfunction "VSS_2_40") (pintype "bidirectional"))
      (node (ref "IC7") (pin "51") (pinfunction "TEST_MODE_51") (pintype "bidirectional"))
      (node (ref "IC7") (pin "6") (pinfunction "VSS_1_6") (pintype "bidirectional"))
      (node (ref "IC7") (pin "60") (pinfunction "VSS_3_60") (pintype "bidirectional"))
      (node (ref "IC7") (pin "64") (pinfunction "NGND_KEL0_64") (pintype "bidirectional"))
      (node (ref "IC7") (pin "70") (pinfunction "VSS_4_70") (pintype "bidirectional"))
      (node (ref "IC7") (pin "85") (pinfunction "VSS_5_85") (pintype "bidirectional"))
      (node (ref "IC8") (pin "2") (pinfunction "GND_2") (pintype "bidirectional"))
      (node (ref "IC8") (pin "5") (pinfunction "EP_5") (pintype "bidirectional"))
      (node (ref "IC9") (pin "12") (pinfunction "VSSQ_2_12") (pintype "bidirectional"))
      (node (ref "IC9") (pin "28") (pinfunction "VSS_1_28") (pintype "bidirectional"))
      (node (ref "IC9") (pin "41") (pinfunction "VSS_2_41") (pintype "bidirectional"))
      (node (ref "IC9") (pin "46") (pinfunction "VSSQ_3_46") (pintype "bidirectional"))
      (node (ref "IC9") (pin "52") (pinfunction "VSSQ_4_52") (pintype "bidirectional"))
      (node (ref "IC9") (pin "54") (pinfunction "VSS_3_54") (pintype "bidirectional"))
      (node (ref "IC9") (pin "6") (pinfunction "VSSQ_1_6") (pintype "bidirectional"))
      (node (ref "J1") (pin "10") (pinfunction "10_10") (pintype "bidirectional"))
      (node (ref "J1") (pin "11") (pinfunction "11_11") (pintype "bidirectional"))
      (node (ref "J1") (pin "12") (pinfunction "12_12") (pintype "bidirectional"))
      (node (ref "J1") (pin "13") (pinfunction "13_13") (pintype "bidirectional"))
      (node (ref "J1") (pin "14") (pinfunction "14_14") (pintype "bidirectional"))
      (node (ref "J1") (pin "15") (pinfunction "15_15") (pintype "bidirectional"))
      (node (ref "J1") (pin "16") (pinfunction "16_16") (pintype "bidirectional"))
      (node (ref "J1") (pin "6") (pinfunction "VSS_6") (pintype "power_in"))
      (node (ref "J2") (pin "1") (pinfunction "1_1") (pintype "bidirectional"))
      (node (ref "J2") (pin "14") (pinfunction "14_14") (pintype "bidirectional"))
      (node (ref "J2") (pin "7") (pinfunction "7_7") (pintype "bidirectional"))
      (node (ref "PS1") (pin "2") (pinfunction "2_2") (pintype "bidirectional"))
      (node (ref "R10") (pin "2") (pinfunction "2_2") (pintype "passive"))
      (node (ref "R2") (pin "1") (pinfunction "1_1") (pintype "passive"))
      (node (ref "R26") (pin "2") (pinfunction "2_2") (pintype "passive"))
      (node (ref "Y1") (pin "2") (pinfunction "NC_1_2") (pintype "bidirectional"))
      (node (ref "Y1") (pin "4") (pinfunction "NC_2_4") (pintype "bidirectional"))
    )
    (net (code "127") (name "Net-(D1-K)") (class "Default")
      (node (ref "C20") (pin "2") (pinfunction "2_2") (pintype "passive"))
      (node (ref "D1") (pin "1") (pinfunction "K_1") (pintype "bidirectional"))
      (node (ref "IC7") (pin "55") (pinfunction "VDD_SNVS_IN_55") (pintype "bidirectional"))
    )
    (net (code "128") (name "Net-(D3-A)") (class "Default")
      (node (ref "D3") (pin "2") (pinfunction "A_2") (pintype "bidirectional"))
      (node (ref "D4") (pin "2") (pinfunction "A_2") (pintype "bidirectional"))
      (node (ref "R60") (pin "1") (pinfunction "1_1") (pintype "passive"))
      (node (ref "R61") (pin "1") (pinfunction "1_1") (pintype "passive"))
    )
    (net (code "129") (name "Net-(IC1-VDD)") (class "Default")
      (node (ref "IC1") (pin "3") (pinfunction "VDD_3") (pintype "bidirectional"))
      (node (ref "R9") (pin "2") (pinfunction "2_2") (pintype "passive"))
    )
    (net (code "130") (name "Net-(IC1-~{RESET})") (class "Default")
      (node (ref "IC1") (pin "2") (pinfunction "~{RESET}_2") (pintype "bidirectional"))
      (node (ref "R8") (pin "1") (pinfunction "1_1") (pintype "passive"))
    )
    (net (code "131") (name "Net-(IC7-DCDC_LP)") (class "Default")
      (node (ref "IC7") (pin "36") (pinfunction "DCDC_LP_36") (pintype "bidirectional"))
      (node (ref "L2") (pin "2") (pinfunction "2_2") (pintype "bidirectional"))
    )
    (net (code "132") (name "Net-(IC7-DCDC_PSWITCH)") (class "Default")
      (node (ref "C44") (pin "2") (pinfunction "2_2") (pintype "passive"))
      (node (ref "IC7") (pin "37") (pinfunction "DCDC_PSWITCH_37") (pintype "bidirectional"))
      (node (ref "R11") (pin "1") (pinfunction "1_1") (pintype "passive"))
    )
    (net (code "133") (name "Net-(IC8-EN)") (class "Default")
      (node (ref "IC8") (pin "1") (pinfunction "EN_1") (pintype "bidirectional"))
      (node (ref "R60") (pin "2") (pinfunction "2_2") (pintype "passive"))
    )
    (net (code "134") (name "Net-(IC9-A10)") (class "Default")
      (node (ref "IC9") (pin "22") (pinfunction "A10_22") (pintype "bidirectional"))
      (node (ref "R48") (pin "1") (pinfunction "1_1") (pintype "passive"))
    )
    (net (code "135") (name "Net-(IC9-BA0)") (class "Default")
      (node (ref "IC9") (pin "20") (pinfunction "BA0_20") (pintype "bidirectional"))
      (node (ref "R46") (pin "1") (pinfunction "1_1") (pintype "passive"))
    )
    (net (code "136") (name "Net-(IC9-BA1)") (class "Default")
      (node (ref "IC9") (pin "21") (pinfunction "BA1_21") (pintype "bidirectional"))
      (node (ref "R47") (pin "1") (pinfunction "1_1") (pintype "passive"))
    )
    (net (code "137") (name "Net-(IC9-CKE)") (class "Default")
      (node (ref "IC9") (pin "37") (pinfunction "CKE_37") (pintype "bidirectional"))
      (node (ref "R22") (pin "2") (pinfunction "2_2") (pintype "passive"))
    )
    (net (code "138") (name "Net-(IC9-CLK)") (class "Default")
      (node (ref "IC9") (pin "38") (pinfunction "CLK_38") (pintype "bidirectional"))
      (node (ref "R21") (pin "2") (pinfunction "2_2") (pintype "passive"))
    )
    (net (code "139") (name "Net-(IC9-DQ0)") (class "Default")
      (node (ref "IC9") (pin "2") (pinfunction "DQ0_2") (pintype "bidirectional"))
      (node (ref "R33") (pin "1") (pinfunction "1_1") (pintype "passive"))
    )
    (net (code "140") (name "Net-(IC9-DQ1)") (class "Default")
      (node (ref "IC9") (pin "5") (pinfunction "DQ1_5") (pintype "bidirectional"))
      (node (ref "R35") (pin "1") (pinfunction "1_1") (pintype "passive"))
    )
    (net (code "141") (name "Net-(IC9-DQ2)") (class "Default")
      (node (ref "IC9") (pin "8") (pinfunction "DQ2_8") (pintype "bidirectional"))
      (node (ref "R37") (pin "1") (pinfunction "1_1") (pintype "passive"))
    )
    (net (code "142") (name "Net-(IC9-DQ3)") (class "Default")
      (node (ref "IC9") (pin "11") (pinfunction "DQ3_11") (pintype "bidirectional"))
      (node (ref "R39") (pin "1") (pinfunction "1_1") (pintype "passive"))
    )
    (net (code "143") (name "Net-(IC9-DQ4)") (class "Default")
      (node (ref "IC9") (pin "44") (pinfunction "DQ4_44") (pintype "bidirectional"))
      (node (ref "R18") (pin "2") (pinfunction "2_2") (pintype "passive"))
    )
    (net (code "144") (name "Net-(IC9-DQ5)") (class "Default")
      (node (ref "IC9") (pin "47") (pinfunction "DQ5_47") (pintype "bidirectional"))
      (node (ref "R16") (pin "2") (pinfunction "2_2") (pintype "passive"))
    )
    (net (code "145") (name "Net-(IC9-DQ6)") (class "Default")
      (node (ref "IC9") (pin "50") (pinfunction "DQ6_50") (pintype "bidirectional"))
      (node (ref "R14") (pin "2") (pinfunction "2_2") (pintype "passive"))
    )
    (net (code "146") (name "Net-(IC9-DQ7)") (class "Default")
      (node (ref "IC9") (pin "53") (pinfunction "DQ7_53") (pintype "bidirectional"))
      (node (ref "R12") (pin "2") (pinfunction "2_2") (pintype "passive"))
    )
    (net (code "147") (name "Net-(IC9-DQM)") (class "Default")
      (node (ref "IC9") (pin "39") (pinfunction "DQM_39") (pintype "bidirectional"))
      (node (ref "R20") (pin "2") (pinfunction "2_2") (pintype "passive"))
    )
    (net (code "148") (name "Net-(IC9-NC_1)") (class "Default")
      (node (ref "IC9") (pin "4") (pinfunction "NC_1_4") (pintype "bidirectional"))
      (node (ref "R34") (pin "1") (pinfunction "1_1") (pintype "passive"))
    )
    (net (code "149") (name "Net-(IC9-NC_2)") (class "Default")
      (node (ref "IC9") (pin "7") (pinfunction "NC_2_7") (pintype "bidirectional"))
      (node (ref "R36") (pin "1") (pinfunction "1_1") (pintype "passive"))
    )
    (net (code "150") (name "Net-(IC9-NC_3)") (class "Default")
      (node (ref "IC9") (pin "10") (pinfunction "NC_3_10") (pintype "bidirectional"))
      (node (ref "R38") (pin "1") (pinfunction "1_1") (pintype "passive"))
    )
    (net (code "151") (name "Net-(IC9-NC_4)") (class "Default")
      (node (ref "IC9") (pin "13") (pinfunction "NC_4_13") (pintype "bidirectional"))
      (node (ref "R40") (pin "1") (pinfunction "1_1") (pintype "passive"))
    )
    (net (code "152") (name "Net-(IC9-NC_5)") (class "Default")
      (node (ref "IC9") (pin "15") (pinfunction "NC_5_15") (pintype "bidirectional"))
      (node (ref "R41") (pin "1") (pinfunction "1_1") (pintype "passive"))
    )
    (net (code "153") (name "Net-(IC9-NC_7)") (class "Default")
      (node (ref "IC9") (pin "42") (pinfunction "NC_7_42") (pintype "bidirectional"))
      (node (ref "R19") (pin "2") (pinfunction "2_2") (pintype "passive"))
    )
    (net (code "154") (name "Net-(IC9-NC_8)") (class "Default")
      (node (ref "IC9") (pin "45") (pinfunction "NC_8_45") (pintype "bidirectional"))
      (node (ref "R17") (pin "2") (pinfunction "2_2") (pintype "passive"))
    )
    (net (code "155") (name "Net-(IC9-NC_9)") (class "Default")
      (node (ref "IC9") (pin "48") (pinfunction "NC_9_48") (pintype "bidirectional"))
      (node (ref "R15") (pin "2") (pinfunction "2_2") (pintype "passive"))
    )
    (net (code "156") (name "Net-(IC9-NC_10)") (class "Default")
      (node (ref "IC9") (pin "51") (pinfunction "NC_10_51") (pintype "bidirectional"))
      (node (ref "R13") (pin "2") (pinfunction "2_2") (pintype "passive"))
    )
    (net (code "157") (name "Net-(IC9-~{CAS})") (class "Default")
      (node (ref "IC9") (pin "17") (pinfunction "~{CAS}_17") (pintype "bidirectional"))
      (node (ref "R43") (pin "1") (pinfunction "1_1") (pintype "passive"))
    )
    (net (code "158") (name "Net-(IC9-~{CS})") (class "Default")
      (node (ref "IC9") (pin "19") (pinfunction "~{CS}_19") (pintype "bidirectional"))
      (node (ref "R45") (pin "1") (pinfunction "1_1") (pintype "passive"))
    )
    (net (code "159") (name "Net-(IC9-~{RAS})") (class "Default")
      (node (ref "IC9") (pin "18") (pinfunction "~{RAS}_18") (pintype "bidirectional"))
      (node (ref "R44") (pin "1") (pinfunction "1_1") (pintype "passive"))
    )
    (net (code "160") (name "Net-(IC9-~{WE})") (class "Default")
      (node (ref "IC9") (pin "16") (pinfunction "~{WE}_16") (pintype "bidirectional"))
      (node (ref "R42") (pin "1") (pinfunction "1_1") (pintype "passive"))
    )
    (net (code "161") (name "Net-(J1-CD{slash}DAT3)") (class "Default")
      (node (ref "J1") (pin "2") (pinfunction "CD/DAT3_2") (pintype "bidirectional"))
      (node (ref "R54") (pin "2") (pinfunction "2_2") (pintype "passive"))
    )
    (net (code "162") (name "Net-(J1-CLK)") (class "Default")
      (node (ref "J1") (pin "5") (pinfunction "CLK_5") (pintype "input"))
      (node (ref "R56") (pin "2") (pinfunction "2_2") (pintype "passive"))
    )
    (net (code "163") (name "Net-(J1-CMD)") (class "Default")
      (node (ref "J1") (pin "3") (pinfunction "CMD_3") (pintype "bidirectional"))
      (node (ref "R55") (pin "2") (pinfunction "2_2") (pintype "passive"))
    )
    (net (code "164") (name "Net-(J1-DAT0)") (class "Default")
      (node (ref "J1") (pin "7") (pinfunction "DAT0_7") (pintype "bidirectional"))
      (node (ref "R57") (pin "2") (pinfunction "2_2") (pintype "passive"))
    )
    (net (code "165") (name "Net-(J1-DAT1)") (class "Default")
      (node (ref "J1") (pin "8") (pinfunction "DAT1_8") (pintype "bidirectional"))
      (node (ref "R58") (pin "2") (pinfunction "2_2") (pintype "passive"))
    )
    (net (code "166") (name "Net-(J1-DATA2)") (class "Default")
      (node (ref "J1") (pin "1") (pinfunction "DATA2_1") (pintype "bidirectional"))
      (node (ref "R53") (pin "2") (pinfunction "2_2") (pintype "passive"))
    )
    (net (code "167") (name "Net-(J2-Pad2)") (class "Default")
      (node (ref "J2") (pin "2") (pinfunction "2_2") (pintype "bidirectional"))
      (node (ref "R27") (pin "1") (pinfunction "1_1") (pintype "passive"))
    )
    (net (code "168") (name "unconnected-(H1-Pad6)") (class "Default")
      (node (ref "H1") (pin "6") (pinfunction "6_6") (pintype "passive"))
    )
    (net (code "169") (name "unconnected-(H1-Pad11)") (class "Default")
      (node (ref "H1") (pin "11") (pinfunction "11_11") (pintype "passive"))
    )
    (net (code "170") (name "unconnected-(H1-Pad13)") (class "Default")
      (node (ref "H1") (pin "13") (pinfunction "13_13") (pintype "passive"))
    )
    (net (code "171") (name "unconnected-(H1-Pad14)") (class "Default")
      (node (ref "H1") (pin "14") (pinfunction "14_14") (pintype "passive"))
    )
    (net (code "172") (name "unconnected-(H1-Pad15)") (class "Default")
      (node (ref "H1") (pin "15") (pinfunction "15_15") (pintype "passive"))
    )
    (net (code "173") (name "unconnected-(H1-Pad17)") (class "Default")
      (node (ref "H1") (pin "17") (pinfunction "17_17") (pintype "passive"))
    )
    (net (code "174") (name "unconnected-(H1-Pad24)") (class "Default")
      (node (ref "H1") (pin "24") (pinfunction "24_24") (pintype "passive"))
    )
    (net (code "175") (name "unconnected-(H1-Pad26)") (class "Default")
      (node (ref "H1") (pin "26") (pinfunction "26_26") (pintype "passive"))
    )
    (net (code "176") (name "unconnected-(H1-Pad27)") (class "Default")
      (node (ref "H1") (pin "27") (pinfunction "27_27") (pintype "passive"))
    )
    (net (code "177") (name "unconnected-(H1-Pad28)") (class "Default")
      (node (ref "H1") (pin "28") (pinfunction "28_28") (pintype "passive"))
    )
    (net (code "178") (name "unconnected-(H1-Pad29)") (class "Default")
      (node (ref "H1") (pin "29") (pinfunction "29_29") (pintype "passive"))
    )
    (net (code "179") (name "unconnected-(H1-Pad30)") (class "Default")
      (node (ref "H1") (pin "30") (pinfunction "30_30") (pintype "passive"))
    )
    (net (code "180") (name "unconnected-(H1-Pad31)") (class "Default")
      (node (ref "H1") (pin "31") (pinfunction "31_31") (pintype "passive"))
    )
    (net (code "181") (name "unconnected-(H1-Pad32)") (class "Default")
      (node (ref "H1") (pin "32") (pinfunction "32_32") (pintype "passive"))
    )
    (net (code "182") (name "unconnected-(H1-Pad33)") (class "Default")
      (node (ref "H1") (pin "33") (pinfunction "33_33") (pintype "passive"))
    )
    (net (code "183") (name "unconnected-(H1-Pad34)") (class "Default")
      (node (ref "H1") (pin "34") (pinfunction "34_34") (pintype "passive"))
    )
    (net (code "184") (name "unconnected-(H1-Pad36)") (class "Default")
      (node (ref "H1") (pin "36") (pinfunction "36_36") (pintype "passive"))
    )
    (net (code "185") (name "unconnected-(H1-Pad38)") (class "Default")
      (node (ref "H1") (pin "38") (pinfunction "38_38") (pintype "passive"))
    )
    (net (code "186") (name "unconnected-(H1-Pad39)") (class "Default")
      (node (ref "H1") (pin "39") (pinfunction "39_39") (pintype "passive"))
    )
    (net (code "187") (name "unconnected-(H1-Pad40)") (class "Default")
      (node (ref "H1") (pin "40") (pinfunction "40_40") (pintype "passive"))
    )
    (net (code "188") (name "unconnected-(H1-Pad41)") (class "Default")
      (node (ref "H1") (pin "41") (pinfunction "41_41") (pintype "passive"))
    )
    (net (code "189") (name "unconnected-(H1-Pad43)") (class "Default")
      (node (ref "H1") (pin "43") (pinfunction "43_43") (pintype "passive"))
    )
    (net (code "190") (name "unconnected-(H1-Pad45)") (class "Default")
      (node (ref "H1") (pin "45") (pinfunction "45_45") (pintype "passive"))
    )
    (net (code "191") (name "unconnected-(H1-Pad46)") (class "Default")
      (node (ref "H1") (pin "46") (pinfunction "46_46") (pintype "passive"))
    )
    (net (code "192") (name "unconnected-(H1-Pad47)") (class "Default")
      (node (ref "H1") (pin "47") (pinfunction "47_47") (pintype "passive"))
    )
    (net (code "193") (name "unconnected-(H1-Pad48)") (class "Default")
      (node (ref "H1") (pin "48") (pinfunction "48_48") (pintype "passive"))
    )
    (net (code "194") (name "unconnected-(H2-Pad1)") (class "Default")
      (node (ref "H2") (pin "1") (pinfunction "1_1") (pintype "passive"))
    )
    (net (code "195") (name "unconnected-(H2-Pad2)") (class "Default")
      (node (ref "H2") (pin "2") (pinfunction "2_2") (pintype "passive"))
    )
    (net (code "196") (name "unconnected-(H2-Pad3)") (class "Default")
      (node (ref "H2") (pin "3") (pinfunction "3_3") (pintype "passive"))
    )
    (net (code "197") (name "unconnected-(H2-Pad4)") (class "Default")
      (node (ref "H2") (pin "4") (pinfunction "4_4") (pintype "passive"))
    )
    (net (code "198") (name "unconnected-(H2-Pad5)") (class "Default")
      (node (ref "H2") (pin "5") (pinfunction "5_5") (pintype "passive"))
    )
    (net (code "199") (name "unconnected-(H2-Pad6)") (class "Default")
      (node (ref "H2") (pin "6") (pinfunction "6_6") (pintype "passive"))
    )
    (net (code "200") (name "unconnected-(H2-Pad7)") (class "Default")
      (node (ref "H2") (pin "7") (pinfunction "7_7") (pintype "passive"))
    )
    (net (code "201") (name "unconnected-(H2-Pad8)") (class "Default")
      (node (ref "H2") (pin "8") (pinfunction "8_8") (pintype "passive"))
    )
    (net (code "202") (name "unconnected-(H2-Pad9)") (class "Default")
      (node (ref "H2") (pin "9") (pinfunction "9_9") (pintype "passive"))
    )
    (net (code "203") (name "unconnected-(H2-Pad11)") (class "Default")
      (node (ref "H2") (pin "11") (pinfunction "11_11") (pintype "passive"))
    )
    (net (code "204") (name "unconnected-(H2-Pad12)") (class "Default")
      (node (ref "H2") (pin "12") (pinfunction "12_12") (pintype "passive"))
    )
    (net (code "205") (name "unconnected-(H2-Pad14)") (class "Default")
      (node (ref "H2") (pin "14") (pinfunction "14_14") (pintype "passive"))
    )
    (net (code "206") (name "unconnected-(H2-Pad15)") (class "Default")
      (node (ref "H2") (pin "15") (pinfunction "15_15") (pintype "passive"))
    )
    (net (code "207") (name "unconnected-(H2-Pad16)") (class "Default")
      (node (ref "H2") (pin "16") (pinfunction "16_16") (pintype "passive"))
    )
    (net (code "208") (name "unconnected-(H2-Pad17)") (class "Default")
      (node (ref "H2") (pin "17") (pinfunction "17_17") (pintype "passive"))
    )
    (net (code "209") (name "unconnected-(H2-Pad19)") (class "Default")
      (node (ref "H2") (pin "19") (pinfunction "19_19") (pintype "passive"))
    )
    (net (code "210") (name "unconnected-(H2-Pad20)") (class "Default")
      (node (ref "H2") (pin "20") (pinfunction "20_20") (pintype "passive"))
    )
    (net (code "211") (name "unconnected-(H2-Pad23)") (class "Default")
      (node (ref "H2") (pin "23") (pinfunction "23_23") (pintype "passive"))
    )
    (net (code "212") (name "unconnected-(H2-Pad24)") (class "Default")
      (node (ref "H2") (pin "24") (pinfunction "24_24") (pintype "passive"))
    )
    (net (code "213") (name "unconnected-(H2-Pad25)") (class "Default")
      (node (ref "H2") (pin "25") (pinfunction "25_25") (pintype "passive"))
    )
    (net (code "214") (name "unconnected-(H2-Pad26)") (class "Default")
      (node (ref "H2") (pin "26") (pinfunction "26_26") (pintype "passive"))
    )
    (net (code "215") (name "unconnected-(H2-Pad32)") (class "Default")
      (node (ref "H2") (pin "32") (pinfunction "32_32") (pintype "passive"))
    )
    (net (code "216") (name "unconnected-(H2-Pad33)") (class "Default")
      (node (ref "H2") (pin "33") (pinfunction "33_33") (pintype "passive"))
    )
    (net (code "217") (name "unconnected-(H2-Pad34)") (class "Default")
      (node (ref "H2") (pin "34") (pinfunction "34_34") (pintype "passive"))
    )
    (net (code "218") (name "unconnected-(H2-Pad35)") (class "Default")
      (node (ref "H2") (pin "35") (pinfunction "35_35") (pintype "passive"))
    )
    (net (code "219") (name "unconnected-(H2-Pad36)") (class "Default")
      (node (ref "H2") (pin "36") (pinfunction "36_36") (pintype "passive"))
    )
    (net (code "220") (name "unconnected-(H2-Pad37)") (class "Default")
      (node (ref "H2") (pin "37") (pinfunction "37_37") (pintype "passive"))
    )
    (net (code "221") (name "unconnected-(H2-Pad38)") (class "Default")
      (node (ref "H2") (pin "38") (pinfunction "38_38") (pintype "passive"))
    )
    (net (code "222") (name "unconnected-(H2-Pad39)") (class "Default")
      (node (ref "H2") (pin "39") (pinfunction "39_39") (pintype "passive"))
    )
    (net (code "223") (name "unconnected-(H2-Pad40)") (class "Default")
      (node (ref "H2") (pin "40") (pinfunction "40_40") (pintype "passive"))
    )
    (net (code "224") (name "unconnected-(H2-Pad41)") (class "Default")
      (node (ref "H2") (pin "41") (pinfunction "41_41") (pintype "passive"))
    )
    (net (code "225") (name "unconnected-(H2-Pad42)") (class "Default")
      (node (ref "H2") (pin "42") (pinfunction "42_42") (pintype "passive"))
    )
    (net (code "226") (name "unconnected-(H2-Pad43)") (class "Default")
      (node (ref "H2") (pin "43") (pinfunction "43_43") (pintype "passive"))
    )
    (net (code "227") (name "unconnected-(H2-Pad44)") (class "Default")
      (node (ref "H2") (pin "44") (pinfunction "44_44") (pintype "passive"))
    )
    (net (code "228") (name "unconnected-(H2-Pad45)") (class "Default")
      (node (ref "H2") (pin "45") (pinfunction "45_45") (pintype "passive"))
    )
    (net (code "229") (name "unconnected-(H2-Pad46)") (class "Default")
      (node (ref "H2") (pin "46") (pinfunction "46_46") (pintype "passive"))
    )
    (net (code "230") (name "unconnected-(H2-Pad49)") (class "Default")
      (node (ref "H2") (pin "49") (pinfunction "49_49") (pintype "passive"))
    )
    (net (code "231") (name "unconnected-(H2-Pad50)") (class "Default")
      (node (ref "H2") (pin "50") (pinfunction "50_50") (pintype "passive"))
    )
    (net (code "232") (name "unconnected-(H2-Pad51)") (class "Default")
      (node (ref "H2") (pin "51") (pinfunction "51_51") (pintype "passive"))
    )
    (net (code "233") (name "unconnected-(IC7-GPIO_AD_B1_13-Pad76)") (class "Default")
      (node (ref "IC7") (pin "76") (pinfunction "GPIO_AD_B1_13_76") (pintype "bidirectional"))
    )
    (net (code "234") (name "unconnected-(IC7-GPIO_EMC_28-Pad128)") (class "Default")
      (node (ref "IC7") (pin "128") (pinfunction "GPIO_EMC_28_128") (pintype "bidirectional"))
    )
    (net (code "235") (name "unconnected-(IC7-GPIO_EMC_40-Pad116)") (class "Default")
      (node (ref "IC7") (pin "116") (pinfunction "GPIO_EMC_40_116") (pintype "bidirectional"))
    )
    (net (code "236") (name "unconnected-(IC7-GPIO_EMC_41-Pad115)") (class "Default")
      (node (ref "IC7") (pin "115") (pinfunction "GPIO_EMC_41_115") (pintype "bidirectional"))
    )
    (net (code "237") (name "unconnected-(IC7-GPIO_SD_B1_00-Pad33)") (class "Default")
      (node (ref "IC7") (pin "33") (pinfunction "GPIO_SD_B1_00_33") (pintype "bidirectional"))
    )
    (net (code "238") (name "unconnected-(IC7-GPIO_SD_B1_01-Pad32)") (class "Default")
      (node (ref "IC7") (pin "32") (pinfunction "GPIO_SD_B1_01_32") (pintype "bidirectional"))
    )
    (net (code "239") (name "unconnected-(IC7-GPIO_SD_B1_02-Pad30)") (class "Default")
      (node (ref "IC7") (pin "30") (pinfunction "GPIO_SD_B1_02_30") (pintype "bidirectional"))
    )
    (net (code "240") (name "unconnected-(IC7-GPIO_SD_B1_03-Pad28)") (class "Default")
      (node (ref "IC7") (pin "28") (pinfunction "GPIO_SD_B1_03_28") (pintype "bidirectional"))
    )
    (net (code "241") (name "unconnected-(IC7-ONOFF-Pad49)") (class "Default")
      (node (ref "IC7") (pin "49") (pinfunction "ONOFF_49") (pintype "bidirectional"))
    )
    (net (code "242") (name "unconnected-(IC7-PMIC_ON_REQ-Pad53)") (class "Default")
      (node (ref "IC7") (pin "53") (pinfunction "PMIC_ON_REQ_53") (pintype "bidirectional"))
    )
    (net (code "243") (name "unconnected-(IC7-USB_OTG1_DN-Pad62)") (class "Default")
      (node (ref "IC7") (pin "62") (pinfunction "USB_OTG1_DN_62") (pintype "bidirectional"))
    )
    (net (code "244") (name "unconnected-(IC7-USB_OTG1_DP-Pad63)") (class "Default")
      (node (ref "IC7") (pin "63") (pinfunction "USB_OTG1_DP_63") (pintype "bidirectional"))
    )
    (net (code "245") (name "unconnected-(IC9-NC_6-Pad40)") (class "Default")
      (node (ref "IC9") (pin "40") (pinfunction "NC_6_40") (pintype "bidirectional"))
    )
    (net (code "246") (name "unconnected-(J2-PadMH1)") (class "Default")
      (node (ref "J2") (pin "MH1") (pinfunction "MH1_MH1") (pintype "bidirectional"))
    )
    (net (code "247") (name "unconnected-(J2-PadMH2)") (class "Default")
      (node (ref "J2") (pin "MH2") (pinfunction "MH2_MH2") (pintype "bidirectional"))
    )
    (net (code "248") (name "unconnected-(J2-PadMP1)") (class "Default")
      (node (ref "J2") (pin "MP1") (pinfunction "MP1_MP1") (pintype "bidirectional"))
    )
    (net (code "249") (name "unconnected-(J2-PadMP2)") (class "Default")
      (node (ref "J2") (pin "MP2") (pinfunction "MP2_MP2") (pintype "bidirectional"))
    )
    (net (code "250") (name "unconnected-(PS1-Pad3)") (class "Default")
      (node (ref "PS1") (pin "3") (pinfunction "3_3") (pintype "bidirectional"))
    )
  )
)
